# FlipDot.net
KiCad netlist of a schematic drawn in EAGLE
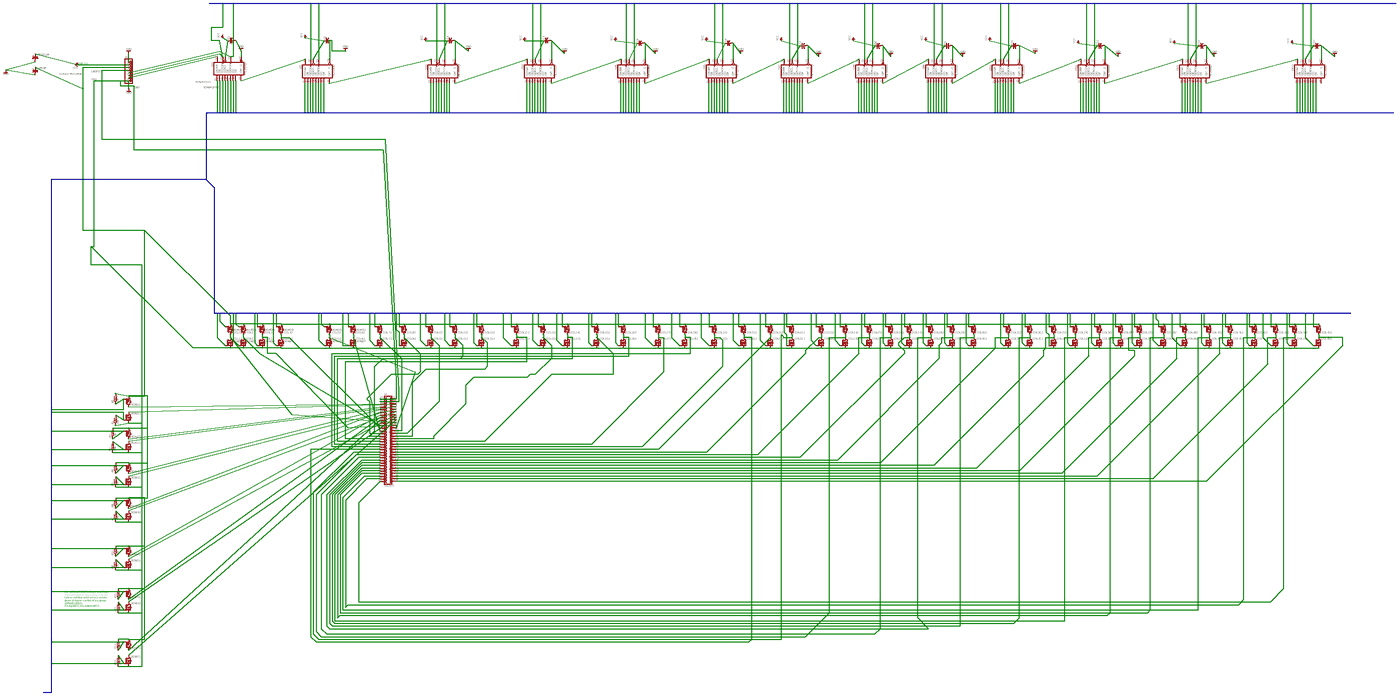
[diagram p0: schematic, sheet 1, overview]
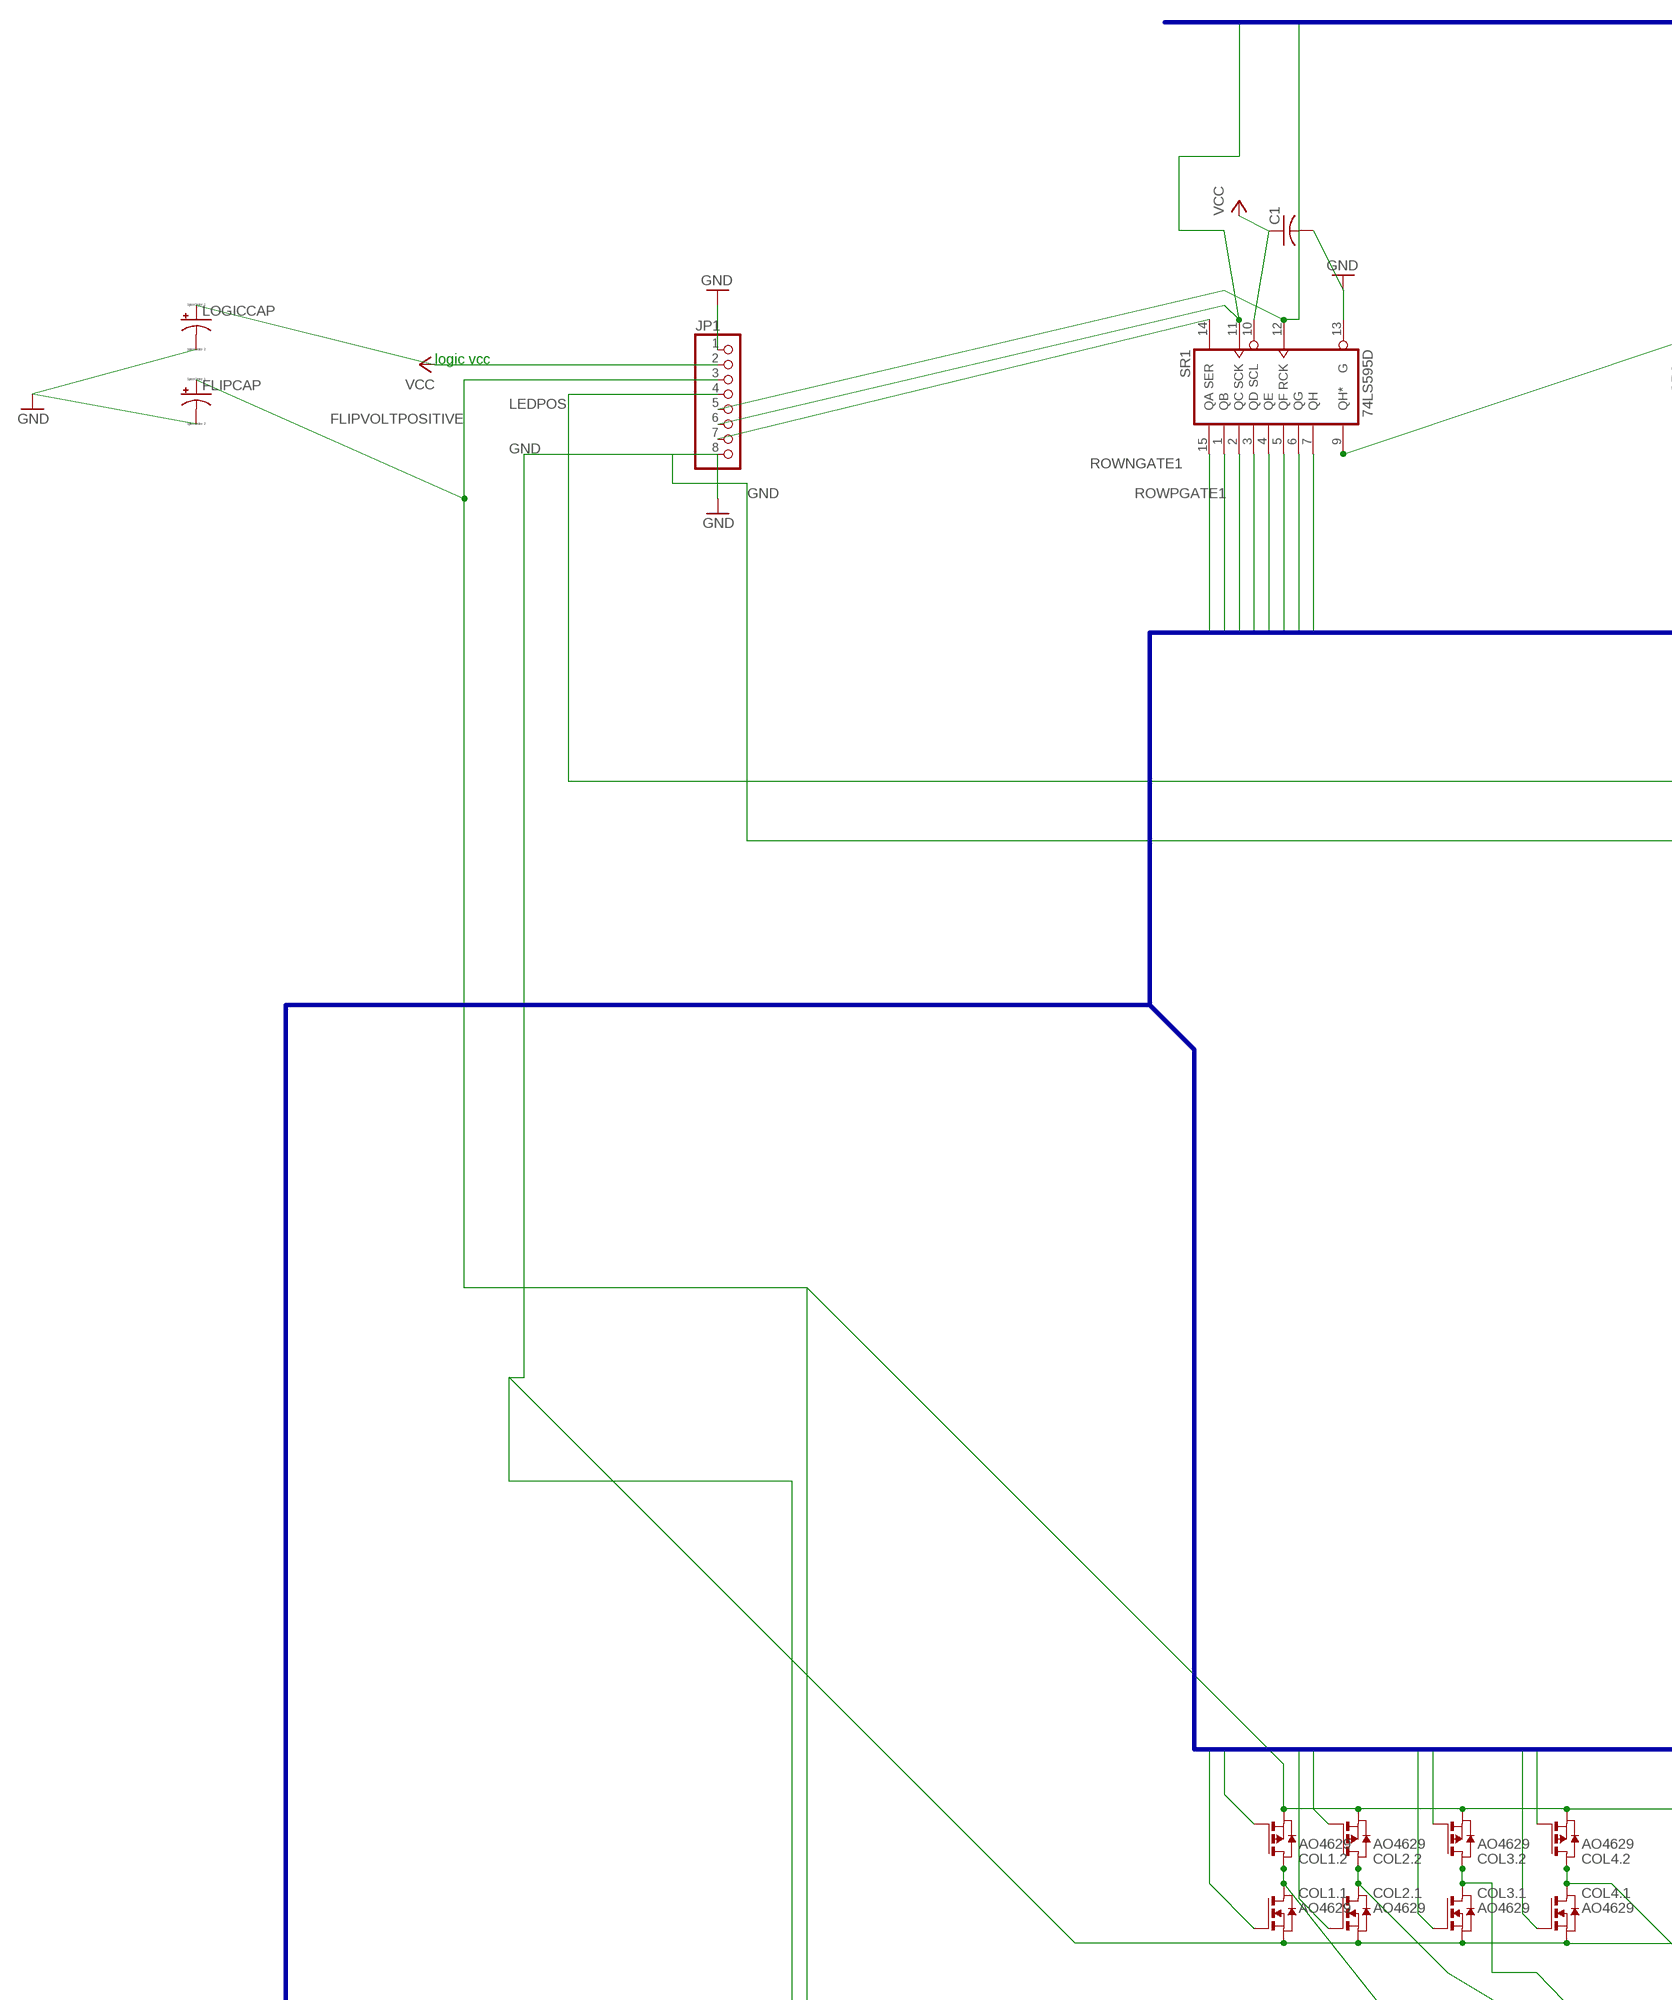
[diagram p1: schematic, sheet 1, part 1 of 8]
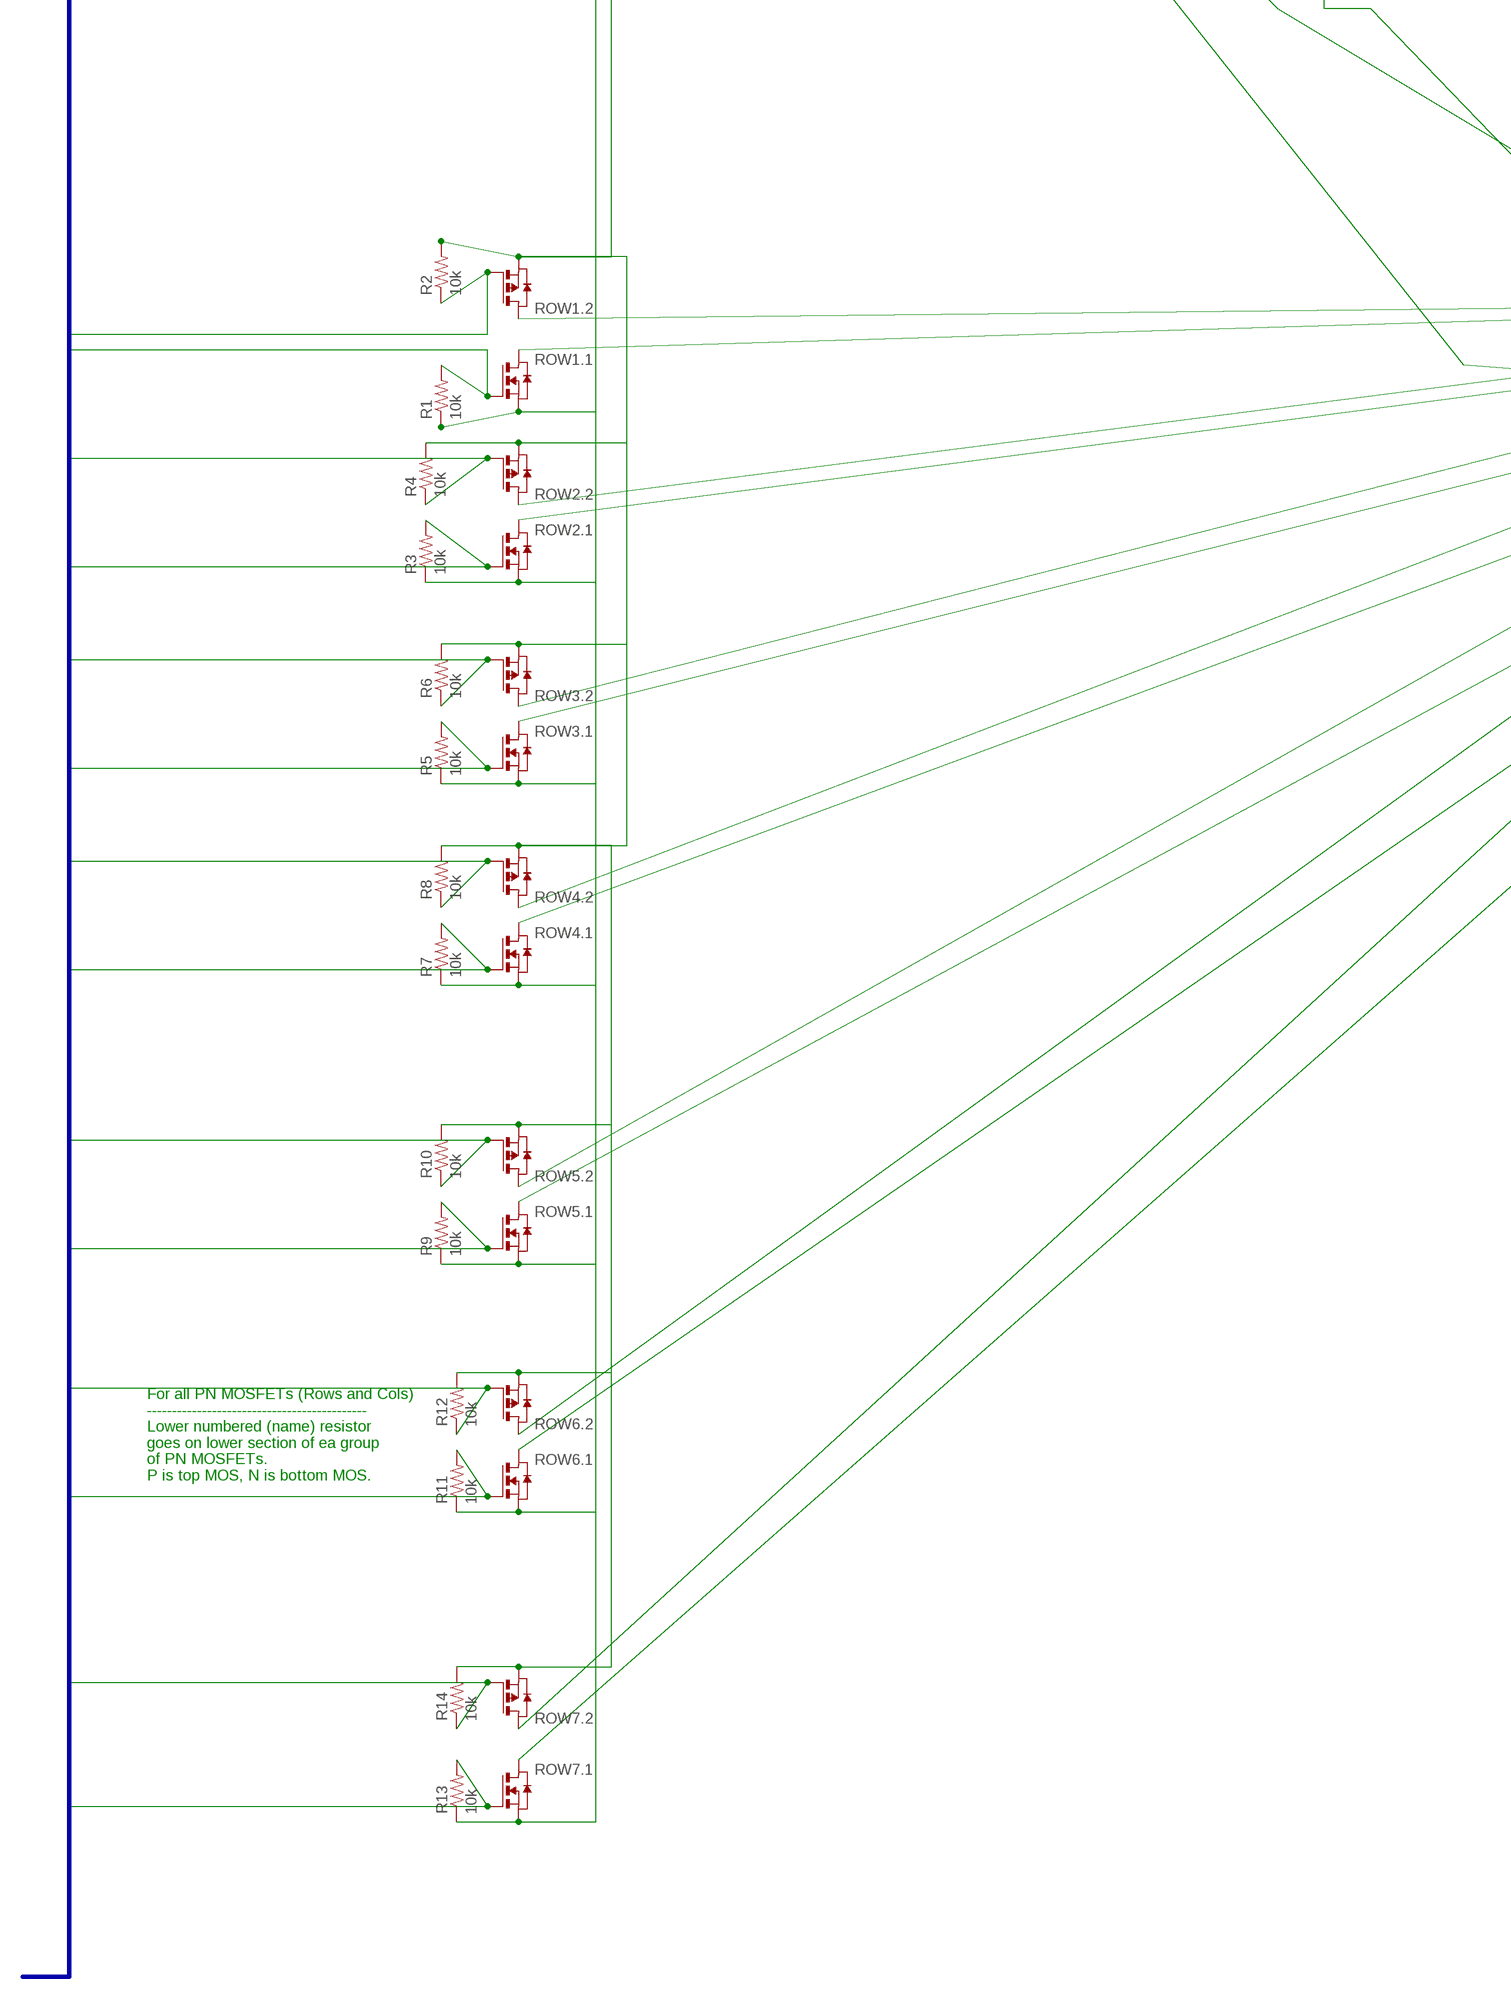
[diagram p2: schematic, sheet 1, part 2 of 8]
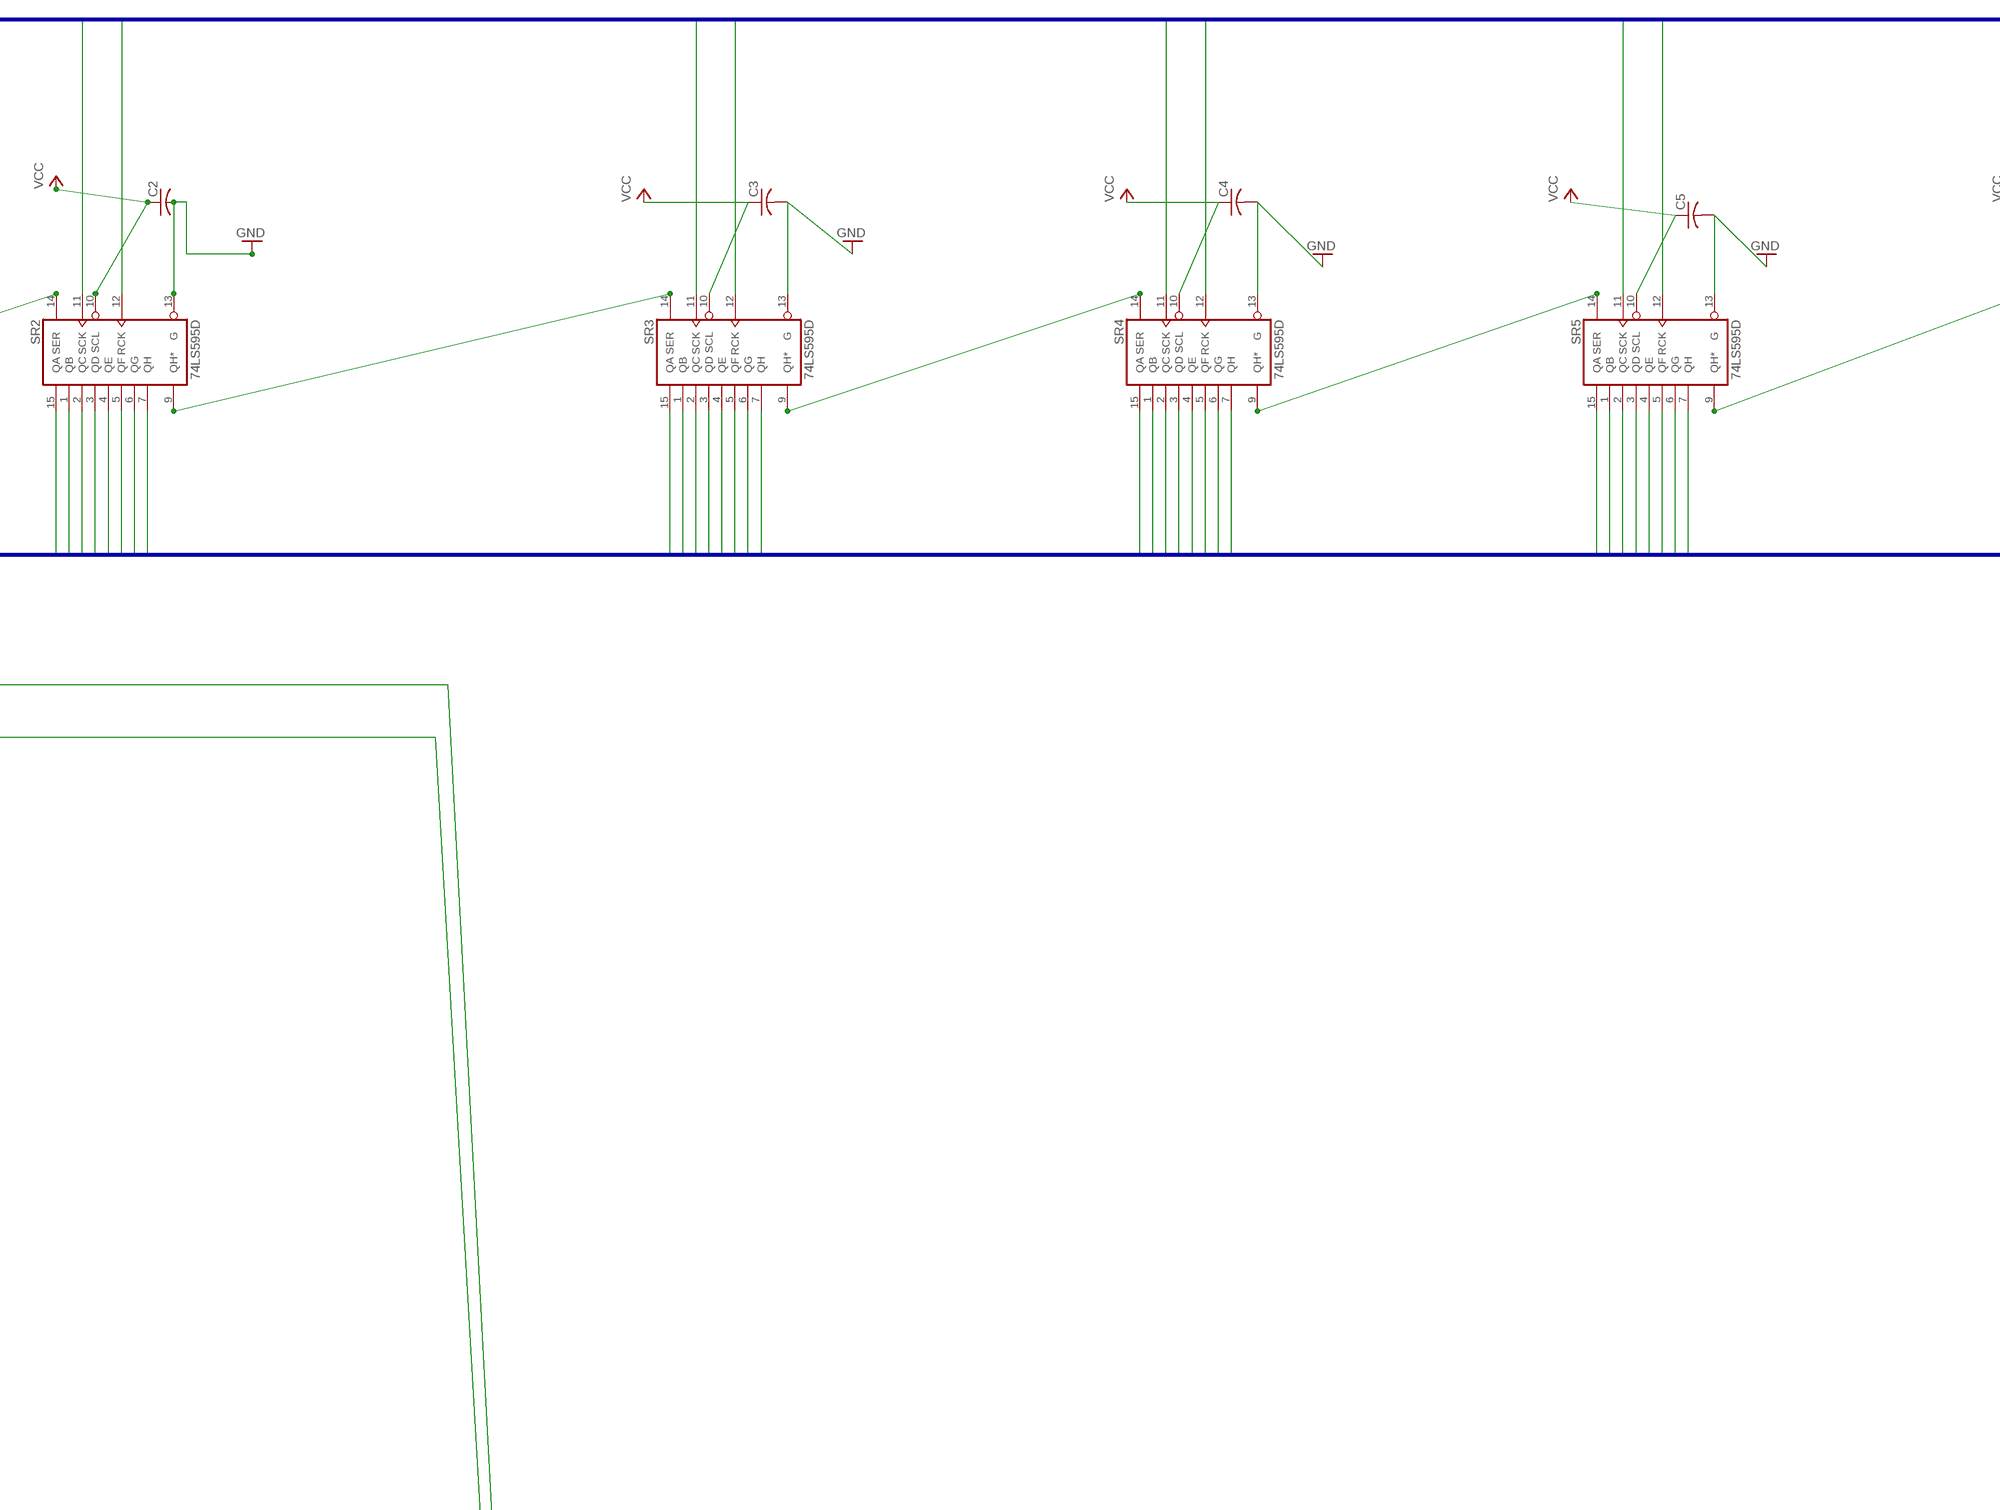
[diagram p3: schematic, sheet 1, part 3 of 8]
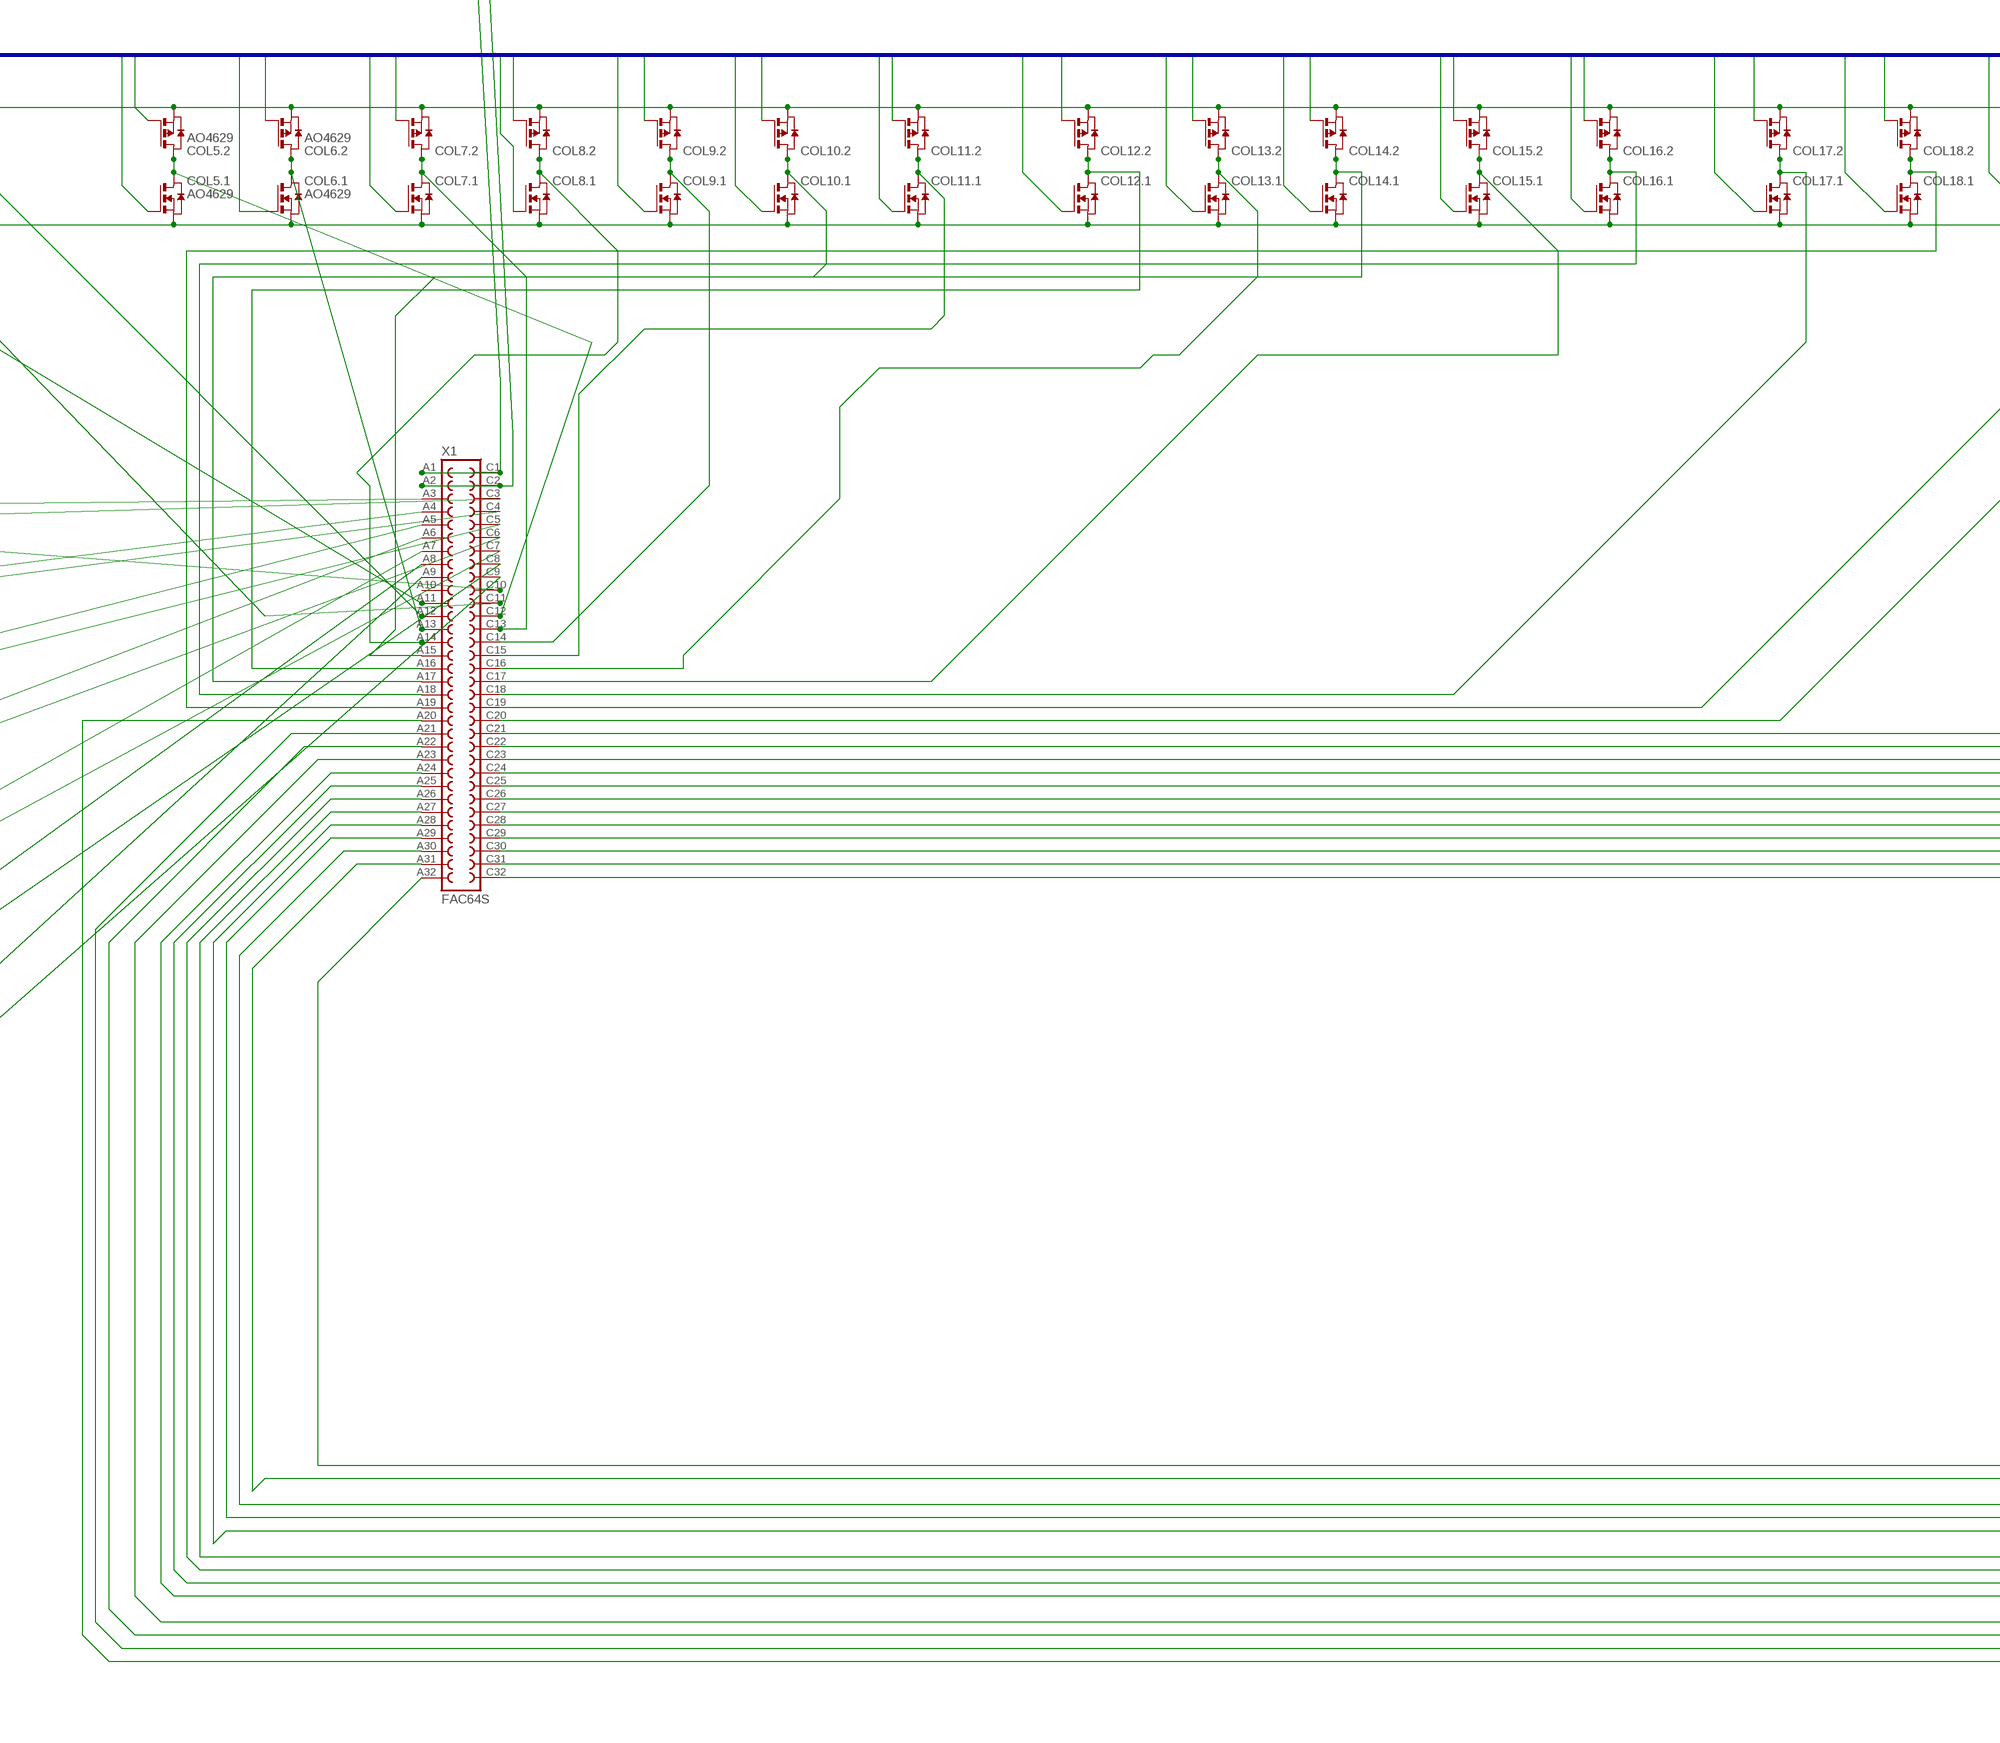
[diagram p4: schematic, sheet 1, part 4 of 8]
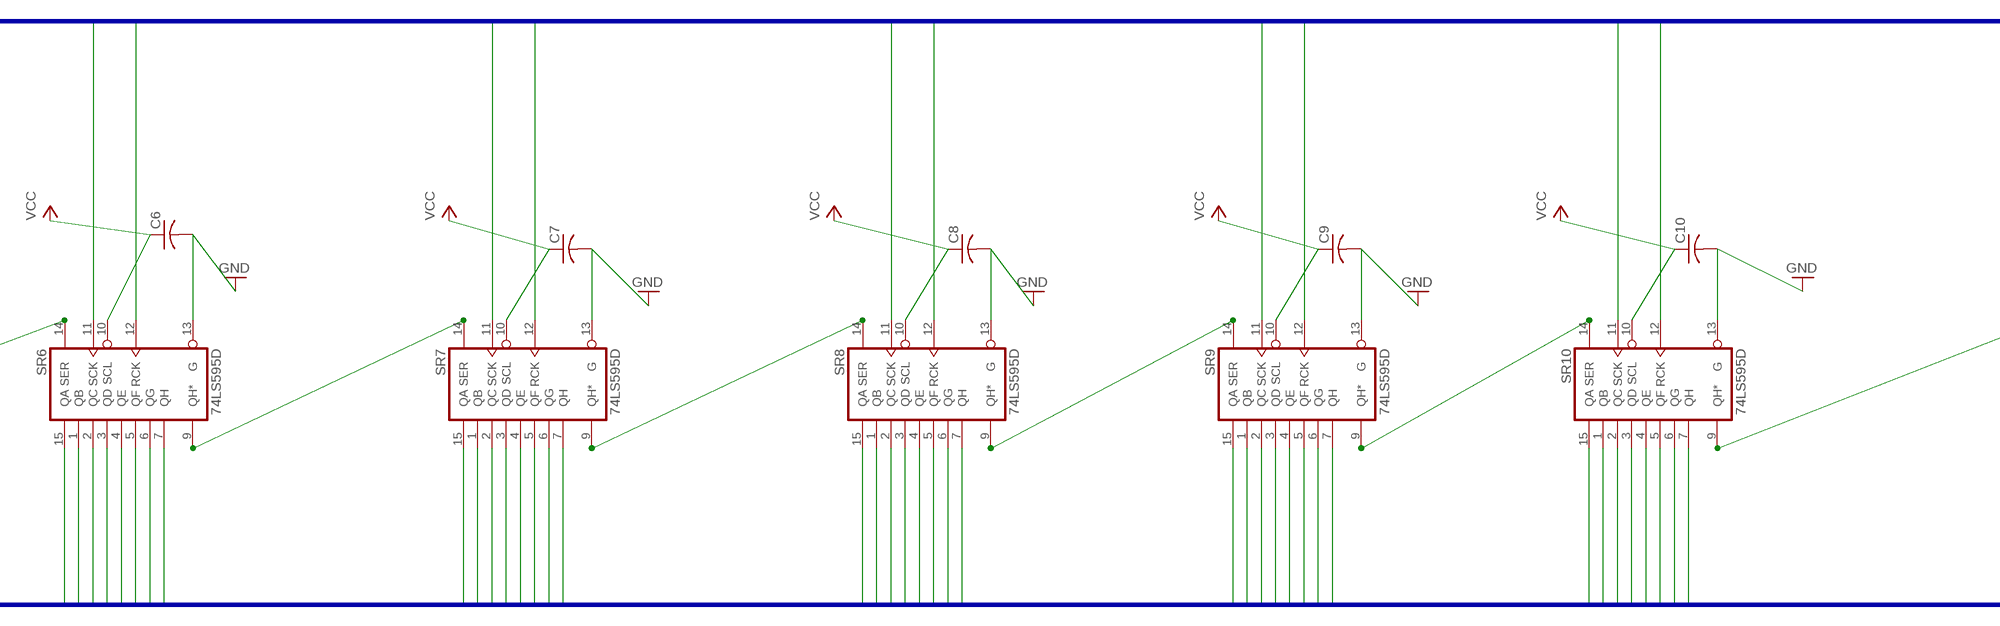
[diagram p5: schematic, sheet 1, part 5 of 8]
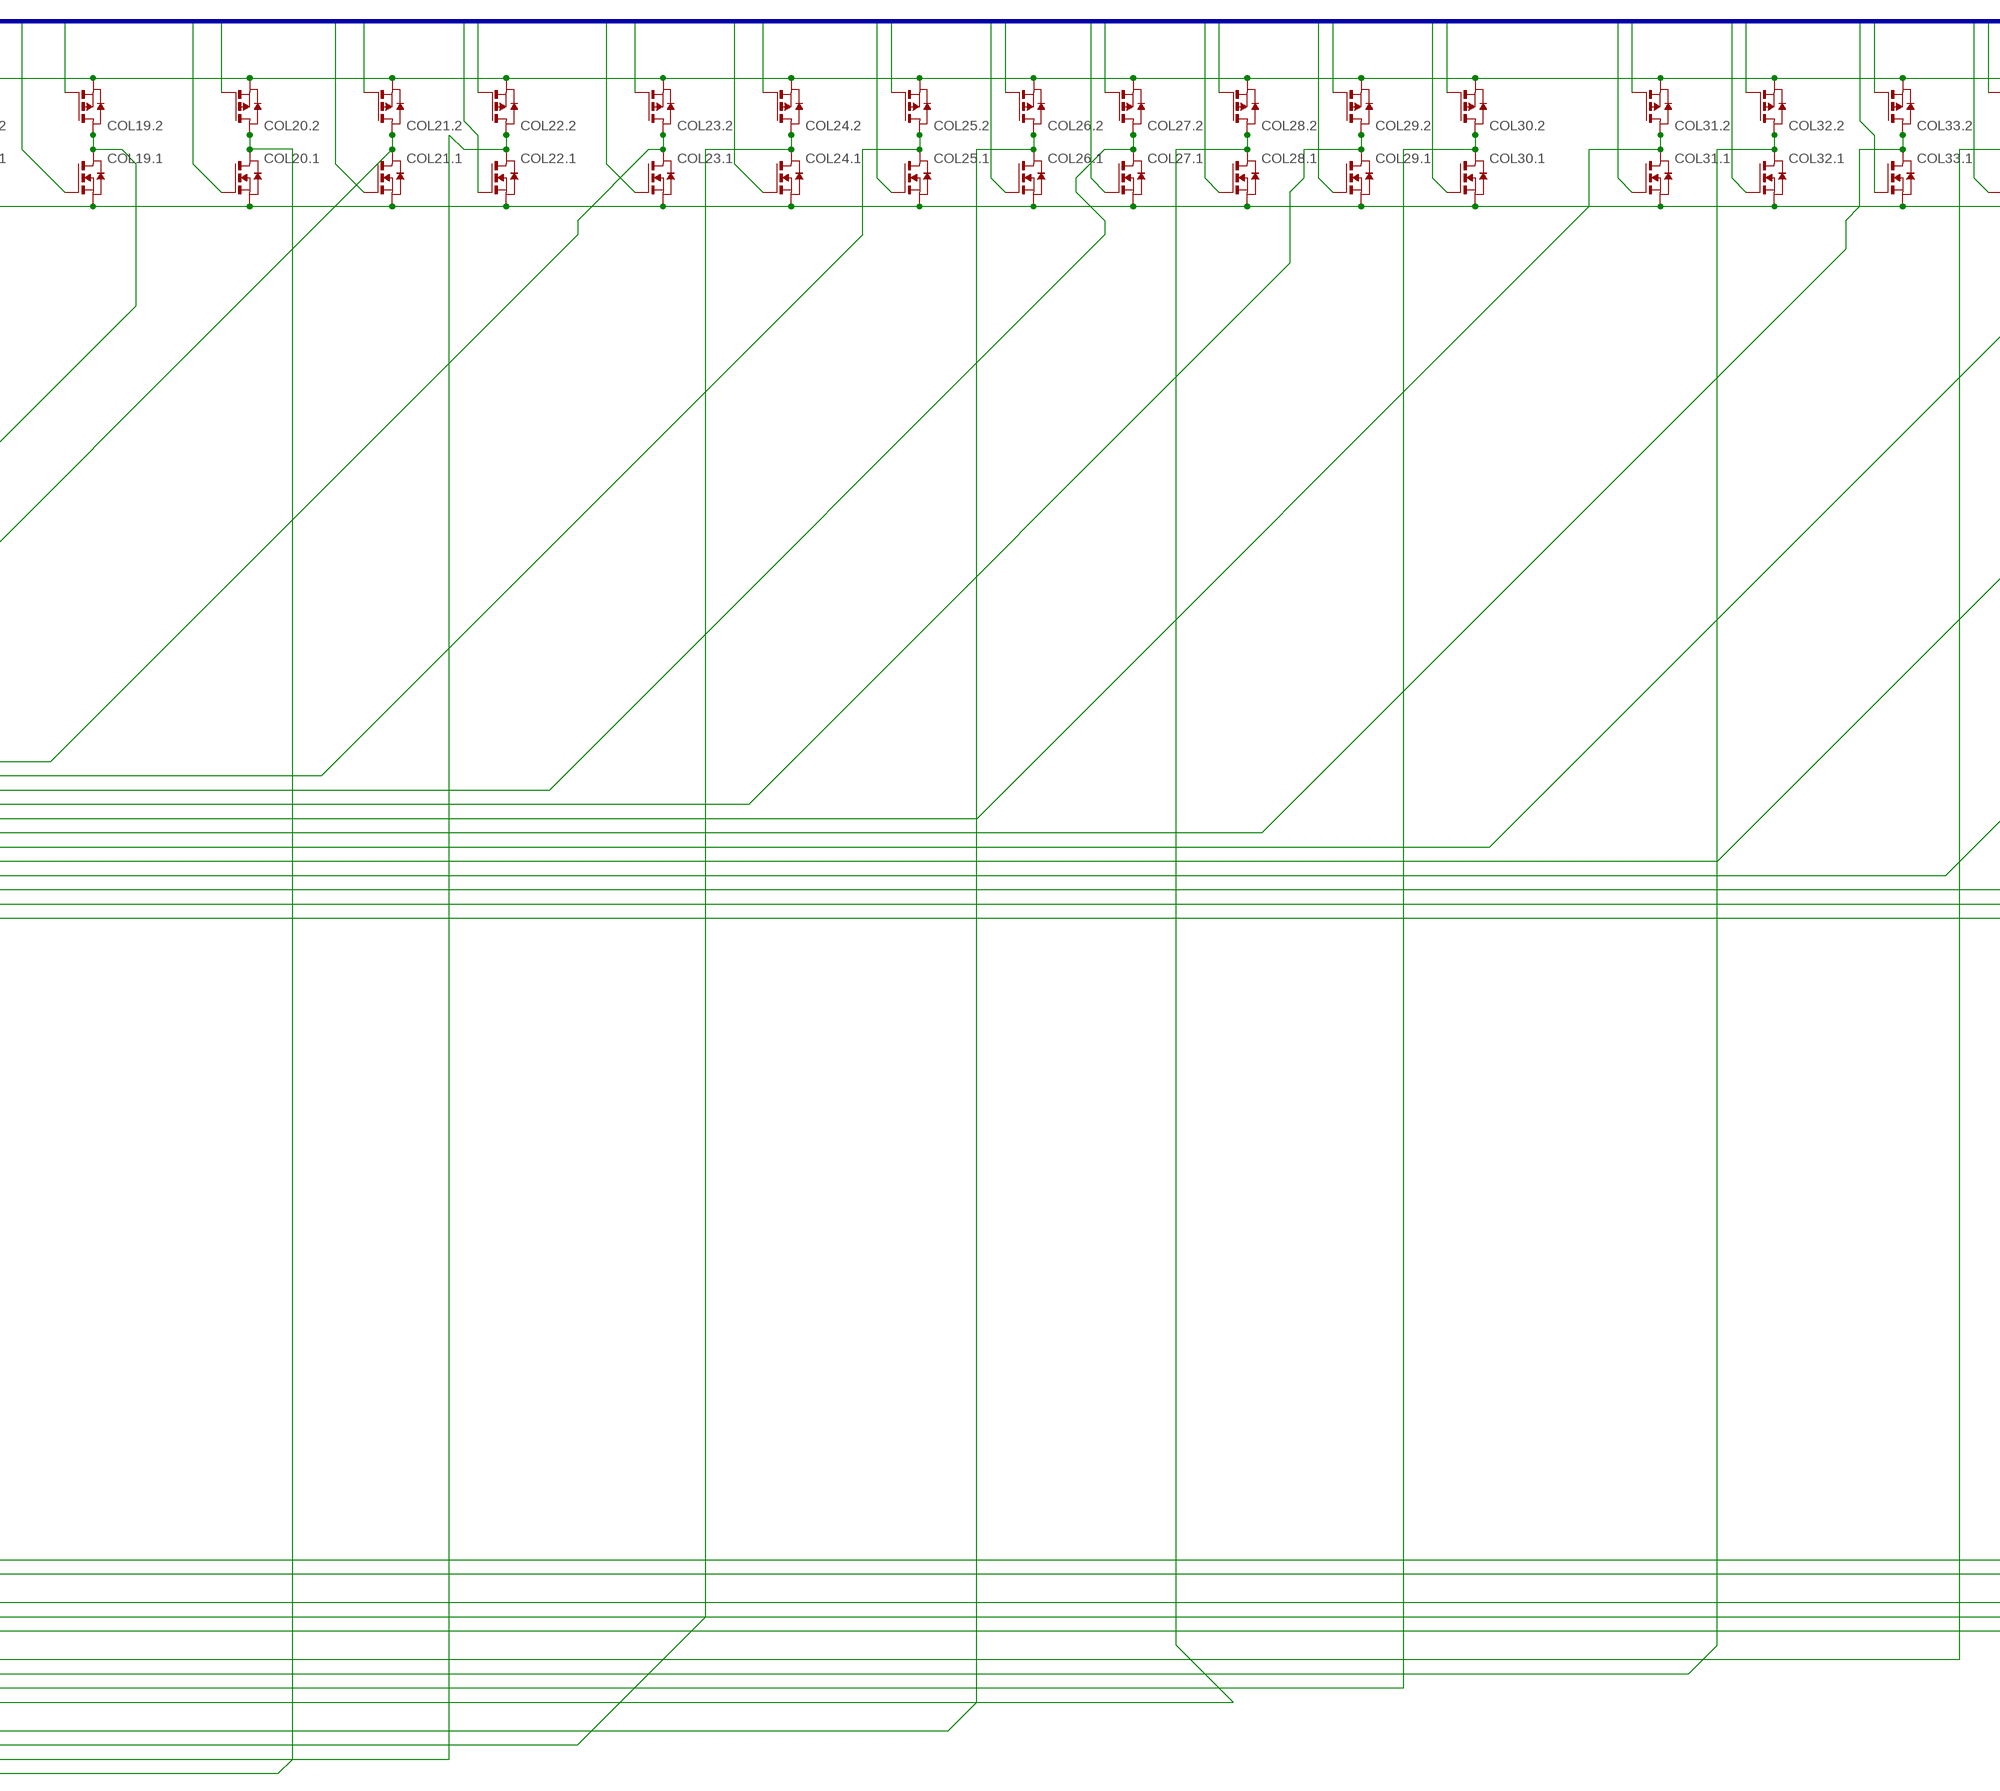
[diagram p6: schematic, sheet 1, part 6 of 8]
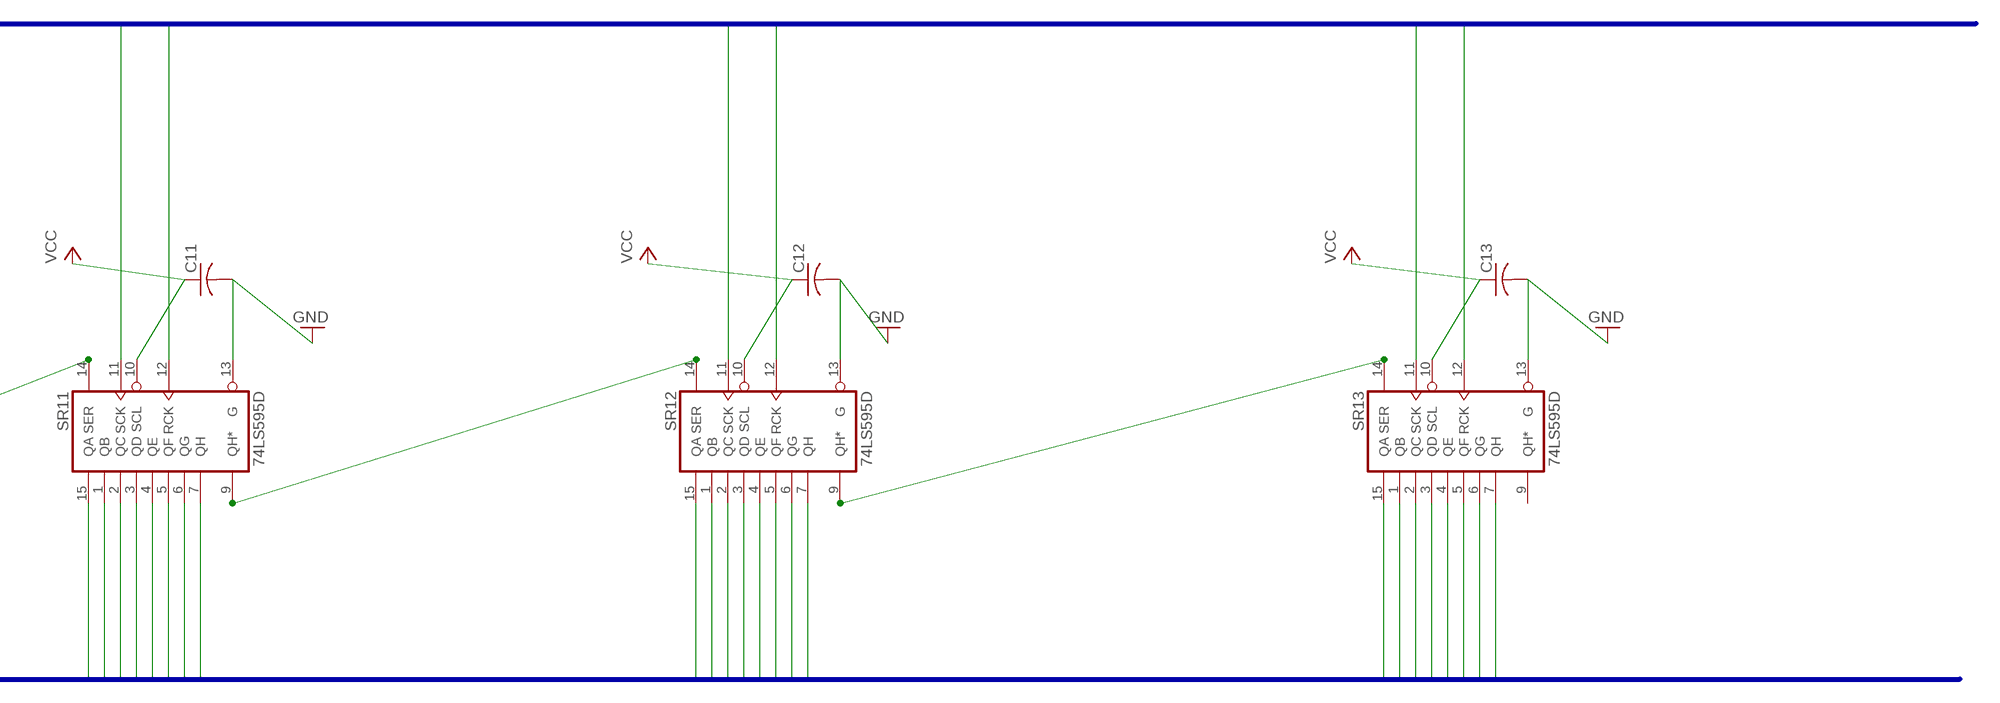
[diagram p7: schematic, sheet 1, part 7 of 8]
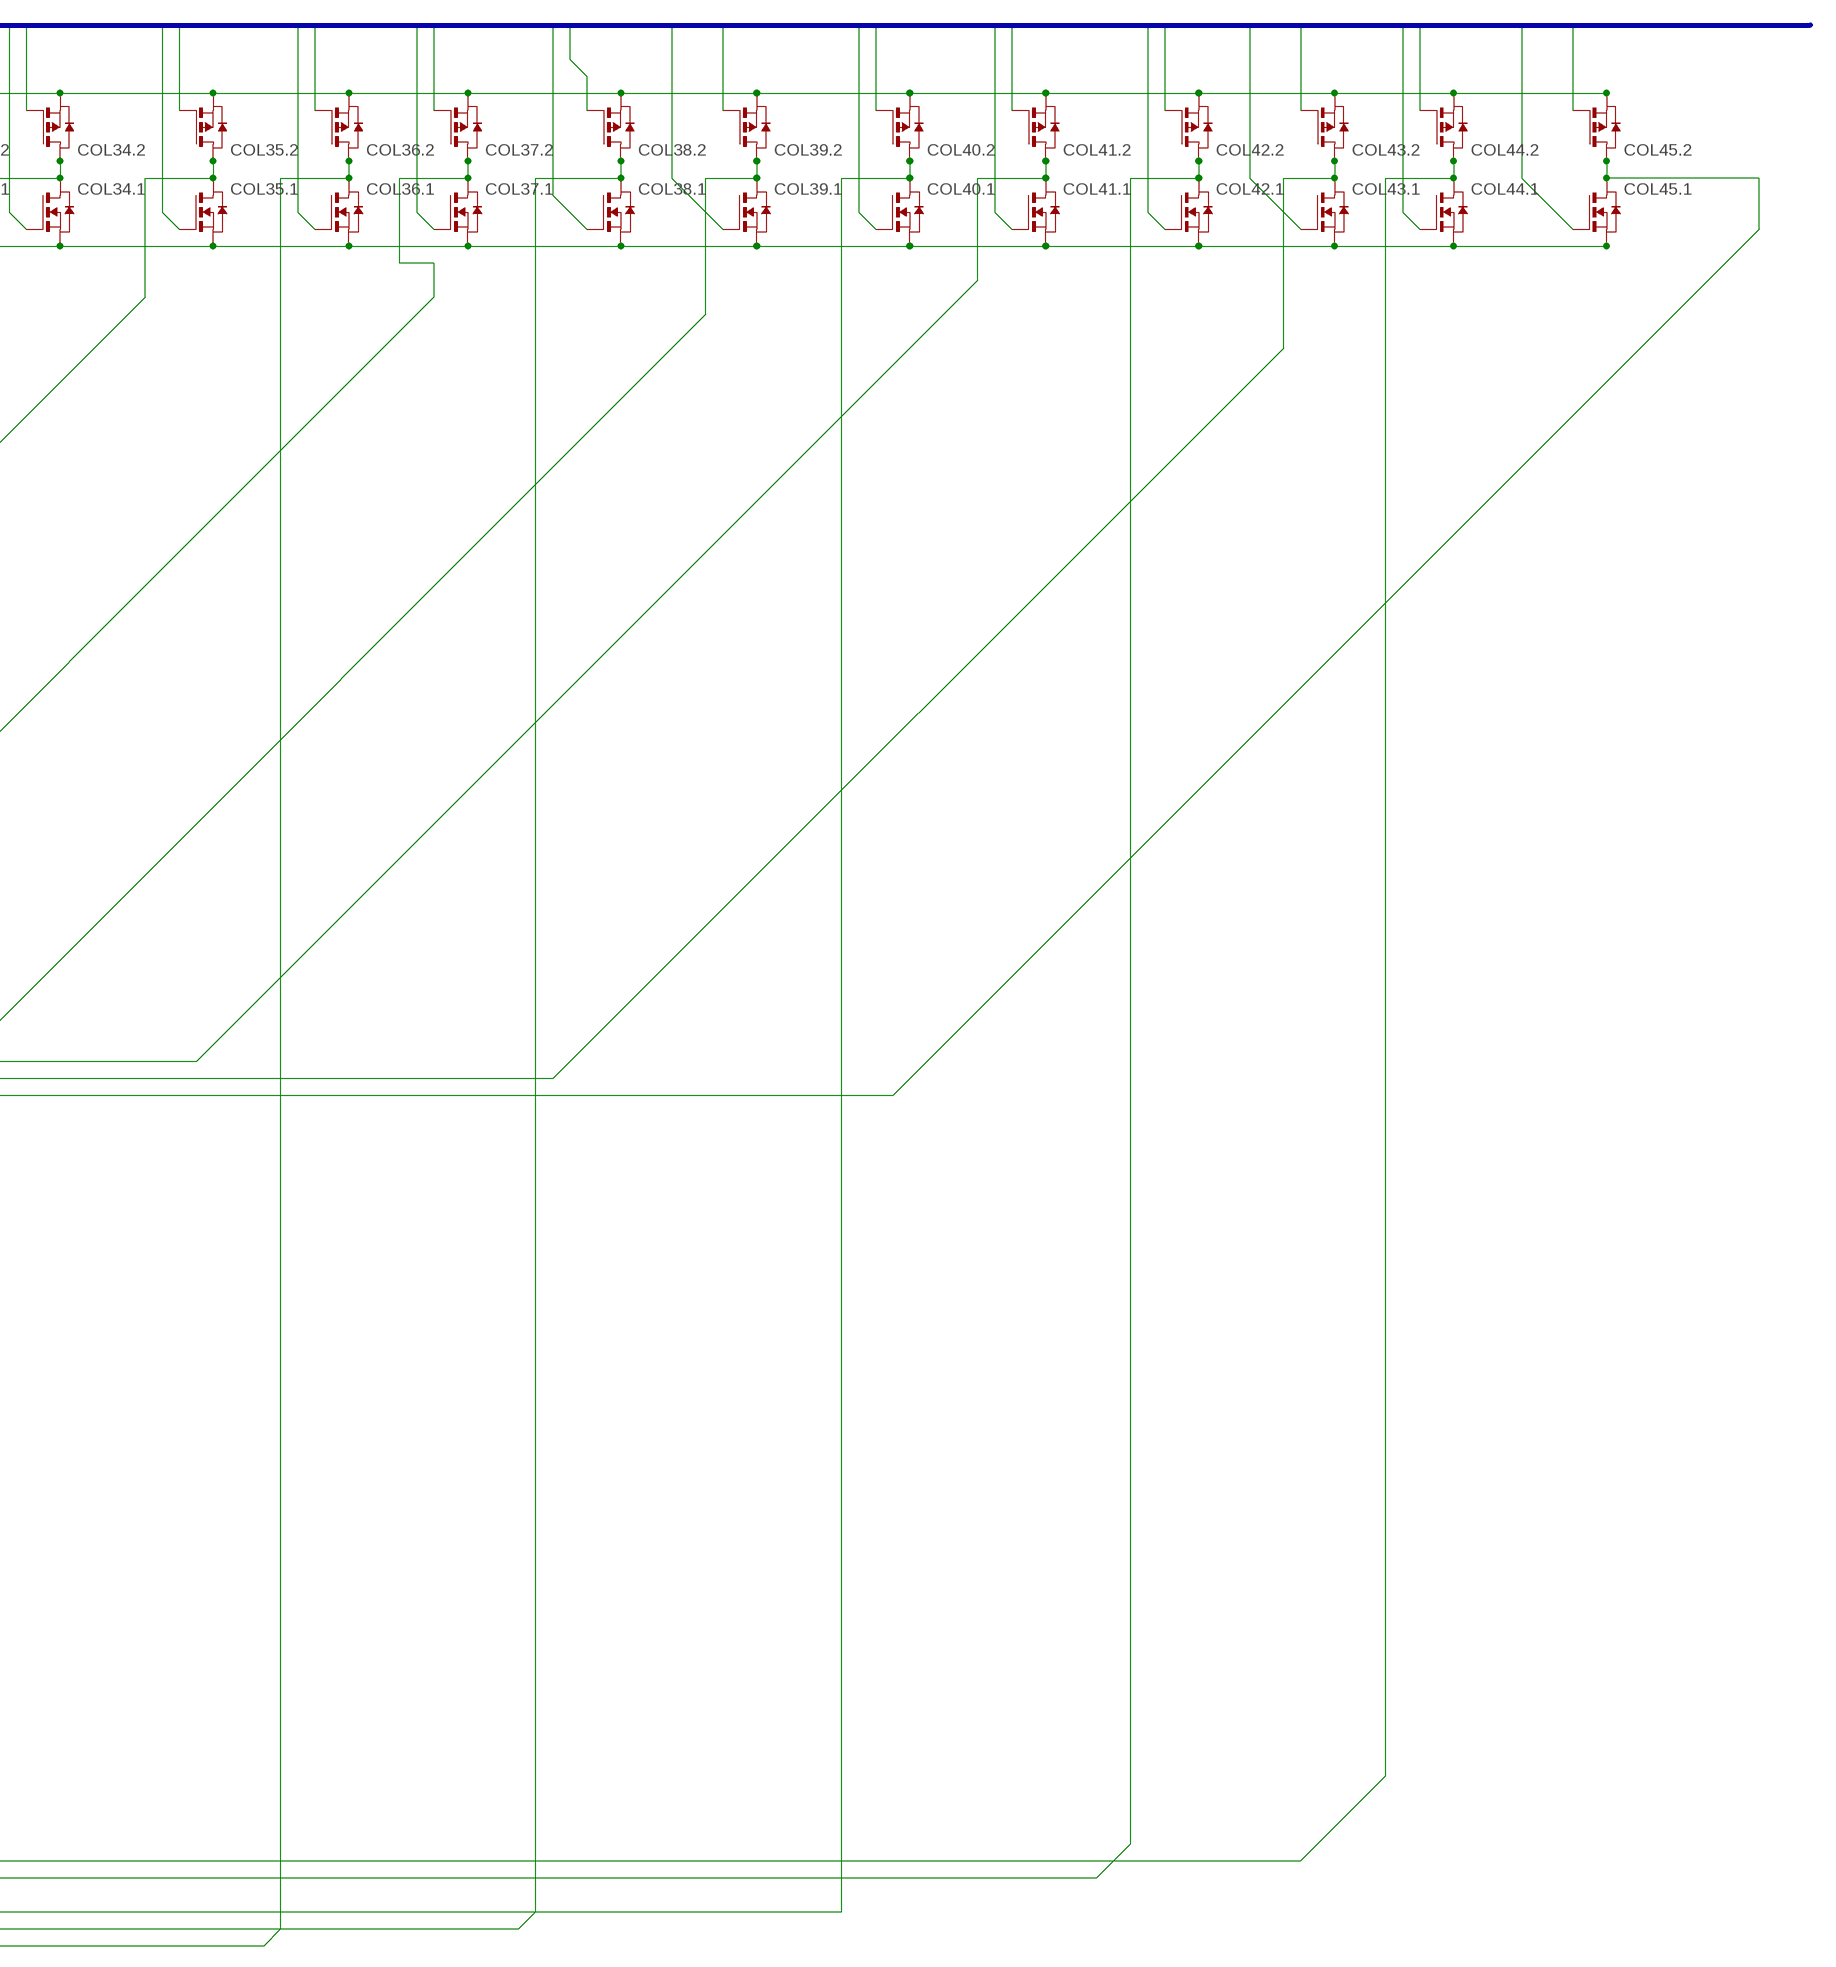
[diagram p8: schematic, sheet 1, part 8 of 8]

(export (version "E")
  (design (tool "Eeschema 10.0.6"))
  (components
    (comp (ref "C1")
      (value "C-USC2012")
      (footprint "eagle-import:C2012")
      (libsource (lib "eagle-import") (part "C-USC2012"))
    )
    (comp (ref "C2")
      (value "C-USC2012")
      (footprint "eagle-import:C2012")
      (libsource (lib "eagle-import") (part "C-USC2012"))
    )
    (comp (ref "C3")
      (value "C-USC2012")
      (footprint "eagle-import:C2012")
      (libsource (lib "eagle-import") (part "C-USC2012"))
    )
    (comp (ref "C4")
      (value "C-USC2012")
      (footprint "eagle-import:C2012")
      (libsource (lib "eagle-import") (part "C-USC2012"))
    )
    (comp (ref "C5")
      (value "C-USC2012")
      (footprint "eagle-import:C2012")
      (libsource (lib "eagle-import") (part "C-USC2012"))
    )
    (comp (ref "C6")
      (value "C-USC2012")
      (footprint "eagle-import:C2012")
      (libsource (lib "eagle-import") (part "C-USC2012"))
    )
    (comp (ref "C7")
      (value "C-USC2012")
      (footprint "eagle-import:C2012")
      (libsource (lib "eagle-import") (part "C-USC2012"))
    )
    (comp (ref "C8")
      (value "C-USC2012")
      (footprint "eagle-import:C2012")
      (libsource (lib "eagle-import") (part "C-USC2012"))
    )
    (comp (ref "C9")
      (value "C-USC2012")
      (footprint "eagle-import:C2012")
      (libsource (lib "eagle-import") (part "C-USC2012"))
    )
    (comp (ref "C10")
      (value "C-USC2012")
      (footprint "eagle-import:C2012")
      (libsource (lib "eagle-import") (part "C-USC2012"))
    )
    (comp (ref "C11")
      (value "C-USC2012")
      (footprint "eagle-import:C2012")
      (libsource (lib "eagle-import") (part "C-USC2012"))
    )
    (comp (ref "C12")
      (value "C-USC2012")
      (footprint "eagle-import:C2012")
      (libsource (lib "eagle-import") (part "C-USC2012"))
    )
    (comp (ref "C13")
      (value "C-USC2012")
      (footprint "eagle-import:C2012")
      (libsource (lib "eagle-import") (part "C-USC2012"))
    )
    (comp (ref "COL1.")
      (value "AO4629")
      (footprint "eagle-import:SO8")
      (libsource (lib "eagle-import") (part "PN_MOSFET-SO8"))
    )
    (comp (ref "COL2.")
      (value "AO4629")
      (footprint "eagle-import:SO8")
      (libsource (lib "eagle-import") (part "PN_MOSFET-SO8"))
    )
    (comp (ref "COL3.")
      (value "AO4629")
      (footprint "eagle-import:SO8")
      (libsource (lib "eagle-import") (part "PN_MOSFET-SO8"))
    )
    (comp (ref "COL4.")
      (value "AO4629")
      (footprint "eagle-import:SO8")
      (libsource (lib "eagle-import") (part "PN_MOSFET-SO8"))
    )
    (comp (ref "COL5.")
      (value "AO4629")
      (footprint "eagle-import:SO8")
      (libsource (lib "eagle-import") (part "PN_MOSFET-SO8"))
    )
    (comp (ref "COL6.")
      (value "AO4629")
      (footprint "eagle-import:SO8")
      (libsource (lib "eagle-import") (part "PN_MOSFET-SO8"))
    )
    (comp (ref "COL7.")
      (value "PN_MOSFET-SO8")
      (footprint "eagle-import:SO8")
      (libsource (lib "eagle-import") (part "PN_MOSFET-SO8"))
    )
    (comp (ref "COL8.")
      (value "PN_MOSFET-SO8")
      (footprint "eagle-import:SO8")
      (libsource (lib "eagle-import") (part "PN_MOSFET-SO8"))
    )
    (comp (ref "COL9.")
      (value "PN_MOSFET-SO8")
      (footprint "eagle-import:SO8")
      (libsource (lib "eagle-import") (part "PN_MOSFET-SO8"))
    )
    (comp (ref "COL10.")
      (value "PN_MOSFET-SO8")
      (footprint "eagle-import:SO8")
      (libsource (lib "eagle-import") (part "PN_MOSFET-SO8"))
    )
    (comp (ref "COL11.")
      (value "PN_MOSFET-SO8")
      (footprint "eagle-import:SO8")
      (libsource (lib "eagle-import") (part "PN_MOSFET-SO8"))
    )
    (comp (ref "COL12.")
      (value "PN_MOSFET-SO8")
      (footprint "eagle-import:SO8")
      (libsource (lib "eagle-import") (part "PN_MOSFET-SO8"))
    )
    (comp (ref "COL13.")
      (value "PN_MOSFET-SO8")
      (footprint "eagle-import:SO8")
      (libsource (lib "eagle-import") (part "PN_MOSFET-SO8"))
    )
    (comp (ref "COL14.")
      (value "PN_MOSFET-SO8")
      (footprint "eagle-import:SO8")
      (libsource (lib "eagle-import") (part "PN_MOSFET-SO8"))
    )
    (comp (ref "COL15.")
      (value "PN_MOSFET-SO8")
      (footprint "eagle-import:SO8")
      (libsource (lib "eagle-import") (part "PN_MOSFET-SO8"))
    )
    (comp (ref "COL16.")
      (value "PN_MOSFET-SO8")
      (footprint "eagle-import:SO8")
      (libsource (lib "eagle-import") (part "PN_MOSFET-SO8"))
    )
    (comp (ref "COL17.")
      (value "PN_MOSFET-SO8")
      (footprint "eagle-import:SO8")
      (libsource (lib "eagle-import") (part "PN_MOSFET-SO8"))
    )
    (comp (ref "COL18.")
      (value "PN_MOSFET-SO8")
      (footprint "eagle-import:SO8")
      (libsource (lib "eagle-import") (part "PN_MOSFET-SO8"))
    )
    (comp (ref "COL19.")
      (value "PN_MOSFET-SO8")
      (footprint "eagle-import:SO8")
      (libsource (lib "eagle-import") (part "PN_MOSFET-SO8"))
    )
    (comp (ref "COL20.")
      (value "PN_MOSFET-SO8")
      (footprint "eagle-import:SO8")
      (libsource (lib "eagle-import") (part "PN_MOSFET-SO8"))
    )
    (comp (ref "COL21.")
      (value "PN_MOSFET-SO8")
      (footprint "eagle-import:SO8")
      (libsource (lib "eagle-import") (part "PN_MOSFET-SO8"))
    )
    (comp (ref "COL22.")
      (value "PN_MOSFET-SO8")
      (footprint "eagle-import:SO8")
      (libsource (lib "eagle-import") (part "PN_MOSFET-SO8"))
    )
    (comp (ref "COL23.")
      (value "PN_MOSFET-SO8")
      (footprint "eagle-import:SO8")
      (libsource (lib "eagle-import") (part "PN_MOSFET-SO8"))
    )
    (comp (ref "COL24.")
      (value "PN_MOSFET-SO8")
      (footprint "eagle-import:SO8")
      (libsource (lib "eagle-import") (part "PN_MOSFET-SO8"))
    )
    (comp (ref "COL25.")
      (value "PN_MOSFET-SO8")
      (footprint "eagle-import:SO8")
      (libsource (lib "eagle-import") (part "PN_MOSFET-SO8"))
    )
    (comp (ref "COL26.")
      (value "PN_MOSFET-SO8")
      (footprint "eagle-import:SO8")
      (libsource (lib "eagle-import") (part "PN_MOSFET-SO8"))
    )
    (comp (ref "COL27.")
      (value "PN_MOSFET-SO8")
      (footprint "eagle-import:SO8")
      (libsource (lib "eagle-import") (part "PN_MOSFET-SO8"))
    )
    (comp (ref "COL28.")
      (value "PN_MOSFET-SO8")
      (footprint "eagle-import:SO8")
      (libsource (lib "eagle-import") (part "PN_MOSFET-SO8"))
    )
    (comp (ref "COL29.")
      (value "PN_MOSFET-SO8")
      (footprint "eagle-import:SO8")
      (libsource (lib "eagle-import") (part "PN_MOSFET-SO8"))
    )
    (comp (ref "COL30.")
      (value "PN_MOSFET-SO8")
      (footprint "eagle-import:SO8")
      (libsource (lib "eagle-import") (part "PN_MOSFET-SO8"))
    )
    (comp (ref "COL31.")
      (value "PN_MOSFET-SO8")
      (footprint "eagle-import:SO8")
      (libsource (lib "eagle-import") (part "PN_MOSFET-SO8"))
    )
    (comp (ref "COL32.")
      (value "PN_MOSFET-SO8")
      (footprint "eagle-import:SO8")
      (libsource (lib "eagle-import") (part "PN_MOSFET-SO8"))
    )
    (comp (ref "COL33.")
      (value "PN_MOSFET-SO8")
      (footprint "eagle-import:SO8")
      (libsource (lib "eagle-import") (part "PN_MOSFET-SO8"))
    )
    (comp (ref "COL34.")
      (value "PN_MOSFET-SO8")
      (footprint "eagle-import:SO8")
      (libsource (lib "eagle-import") (part "PN_MOSFET-SO8"))
    )
    (comp (ref "COL35.")
      (value "PN_MOSFET-SO8")
      (footprint "eagle-import:SO8")
      (libsource (lib "eagle-import") (part "PN_MOSFET-SO8"))
    )
    (comp (ref "COL36.")
      (value "PN_MOSFET-SO8")
      (footprint "eagle-import:SO8")
      (libsource (lib "eagle-import") (part "PN_MOSFET-SO8"))
    )
    (comp (ref "COL37.")
      (value "PN_MOSFET-SO8")
      (footprint "eagle-import:SO8")
      (libsource (lib "eagle-import") (part "PN_MOSFET-SO8"))
    )
    (comp (ref "COL38.")
      (value "PN_MOSFET-SO8")
      (footprint "eagle-import:SO8")
      (libsource (lib "eagle-import") (part "PN_MOSFET-SO8"))
    )
    (comp (ref "COL39.")
      (value "PN_MOSFET-SO8")
      (footprint "eagle-import:SO8")
      (libsource (lib "eagle-import") (part "PN_MOSFET-SO8"))
    )
    (comp (ref "COL40.")
      (value "PN_MOSFET-SO8")
      (footprint "eagle-import:SO8")
      (libsource (lib "eagle-import") (part "PN_MOSFET-SO8"))
    )
    (comp (ref "COL41.")
      (value "PN_MOSFET-SO8")
      (footprint "eagle-import:SO8")
      (libsource (lib "eagle-import") (part "PN_MOSFET-SO8"))
    )
    (comp (ref "COL42.")
      (value "PN_MOSFET-SO8")
      (footprint "eagle-import:SO8")
      (libsource (lib "eagle-import") (part "PN_MOSFET-SO8"))
    )
    (comp (ref "COL43.")
      (value "PN_MOSFET-SO8")
      (footprint "eagle-import:SO8")
      (libsource (lib "eagle-import") (part "PN_MOSFET-SO8"))
    )
    (comp (ref "COL44.")
      (value "PN_MOSFET-SO8")
      (footprint "eagle-import:SO8")
      (libsource (lib "eagle-import") (part "PN_MOSFET-SO8"))
    )
    (comp (ref "COL45.")
      (value "PN_MOSFET-SO8")
      (footprint "eagle-import:SO8")
      (libsource (lib "eagle-import") (part "PN_MOSFET-SO8"))
    )
    (comp (ref "FLIPCAP")
      (value "CPOL-USE5-10.5")
      (footprint "eagle-import:E5-10,5")
      (libsource (lib "eagle-import") (part "CPOL-USE5-10.5"))
    )
    (comp (ref "JP1")
      (value "PINHD-1X8")
      (footprint "eagle-import:1X08")
      (libsource (lib "eagle-import") (part "PINHD-1X8"))
    )
    (comp (ref "LOGICCAP")
      (value "CPOL-USE5-10.5")
      (footprint "eagle-import:E5-10,5")
      (libsource (lib "eagle-import") (part "CPOL-USE5-10.5"))
    )
    (comp (ref "R1")
      (value "10k")
      (footprint "eagle-import:R2012")
      (libsource (lib "eagle-import") (part "R-US_R2012"))
    )
    (comp (ref "R2")
      (value "10k")
      (footprint "eagle-import:R2012")
      (libsource (lib "eagle-import") (part "R-US_R2012"))
    )
    (comp (ref "R3")
      (value "10k")
      (footprint "eagle-import:R2012")
      (libsource (lib "eagle-import") (part "R-US_R2012"))
    )
    (comp (ref "R4")
      (value "10k")
      (footprint "eagle-import:R2012")
      (libsource (lib "eagle-import") (part "R-US_R2012"))
    )
    (comp (ref "R5")
      (value "10k")
      (footprint "eagle-import:R2012")
      (libsource (lib "eagle-import") (part "R-US_R2012"))
    )
    (comp (ref "R6")
      (value "10k")
      (footprint "eagle-import:R2012")
      (libsource (lib "eagle-import") (part "R-US_R2012"))
    )
    (comp (ref "R7")
      (value "10k")
      (footprint "eagle-import:R2012")
      (libsource (lib "eagle-import") (part "R-US_R2012"))
    )
    (comp (ref "R8")
      (value "10k")
      (footprint "eagle-import:R2012")
      (libsource (lib "eagle-import") (part "R-US_R2012"))
    )
    (comp (ref "R9")
      (value "10k")
      (footprint "eagle-import:R2012")
      (libsource (lib "eagle-import") (part "R-US_R2012"))
    )
    (comp (ref "R10")
      (value "10k")
      (footprint "eagle-import:R2012")
      (libsource (lib "eagle-import") (part "R-US_R2012"))
    )
    (comp (ref "R11")
      (value "10k")
      (footprint "eagle-import:R2012")
      (libsource (lib "eagle-import") (part "R-US_R2012"))
    )
    (comp (ref "R12")
      (value "10k")
      (footprint "eagle-import:R2012")
      (libsource (lib "eagle-import") (part "R-US_R2012"))
    )
    (comp (ref "R13")
      (value "10k")
      (footprint "eagle-import:R2012")
      (libsource (lib "eagle-import") (part "R-US_R2012"))
    )
    (comp (ref "R14")
      (value "10k")
      (footprint "eagle-import:R2012")
      (libsource (lib "eagle-import") (part "R-US_R2012"))
    )
    (comp (ref "ROW1.")
      (value "PN_MOSFET-SO8")
      (footprint "eagle-import:SO8")
      (libsource (lib "eagle-import") (part "PN_MOSFET-SO8"))
    )
    (comp (ref "ROW2.")
      (value "PN_MOSFET-SO8")
      (footprint "eagle-import:SO8")
      (libsource (lib "eagle-import") (part "PN_MOSFET-SO8"))
    )
    (comp (ref "ROW3.")
      (value "PN_MOSFET-SO8")
      (footprint "eagle-import:SO8")
      (libsource (lib "eagle-import") (part "PN_MOSFET-SO8"))
    )
    (comp (ref "ROW4.")
      (value "PN_MOSFET-SO8")
      (footprint "eagle-import:SO8")
      (libsource (lib "eagle-import") (part "PN_MOSFET-SO8"))
    )
    (comp (ref "ROW5.")
      (value "PN_MOSFET-SO8")
      (footprint "eagle-import:SO8")
      (libsource (lib "eagle-import") (part "PN_MOSFET-SO8"))
    )
    (comp (ref "ROW6.")
      (value "PN_MOSFET-SO8")
      (footprint "eagle-import:SO8")
      (libsource (lib "eagle-import") (part "PN_MOSFET-SO8"))
    )
    (comp (ref "ROW7.")
      (value "PN_MOSFET-SO8")
      (footprint "eagle-import:SO8")
      (libsource (lib "eagle-import") (part "PN_MOSFET-SO8"))
    )
    (comp (ref "SR1")
      (value "74LS595D")
      (footprint "eagle-import:SO16")
      (libsource (lib "eagle-import") (part "74595DLS"))
    )
    (comp (ref "SR2")
      (value "74LS595D")
      (footprint "eagle-import:SO16")
      (libsource (lib "eagle-import") (part "74595DLS"))
    )
    (comp (ref "SR3")
      (value "74LS595D")
      (footprint "eagle-import:SO16")
      (libsource (lib "eagle-import") (part "74595DLS"))
    )
    (comp (ref "SR4")
      (value "74LS595D")
      (footprint "eagle-import:SO16")
      (libsource (lib "eagle-import") (part "74595DLS"))
    )
    (comp (ref "SR5")
      (value "74LS595D")
      (footprint "eagle-import:SO16")
      (libsource (lib "eagle-import") (part "74595DLS"))
    )
    (comp (ref "SR6")
      (value "74LS595D")
      (footprint "eagle-import:SO16")
      (libsource (lib "eagle-import") (part "74595DLS"))
    )
    (comp (ref "SR7")
      (value "74LS595D")
      (footprint "eagle-import:SO16")
      (libsource (lib "eagle-import") (part "74595DLS"))
    )
    (comp (ref "SR8")
      (value "74LS595D")
      (footprint "eagle-import:SO16")
      (libsource (lib "eagle-import") (part "74595DLS"))
    )
    (comp (ref "SR9")
      (value "74LS595D")
      (footprint "eagle-import:SO16")
      (libsource (lib "eagle-import") (part "74595DLS"))
    )
    (comp (ref "SR10")
      (value "74LS595D")
      (footprint "eagle-import:SO16")
      (libsource (lib "eagle-import") (part "74595DLS"))
    )
    (comp (ref "SR11")
      (value "74LS595D")
      (footprint "eagle-import:SO16")
      (libsource (lib "eagle-import") (part "74595DLS"))
    )
    (comp (ref "SR12")
      (value "74LS595D")
      (footprint "eagle-import:SO16")
      (libsource (lib "eagle-import") (part "74595DLS"))
    )
    (comp (ref "SR13")
      (value "74LS595D")
      (footprint "eagle-import:SO16")
      (libsource (lib "eagle-import") (part "74595DLS"))
    )
    (comp (ref "X1")
      (value "FAC64S")
      (footprint "eagle-import:FAC64S")
      (libsource (lib "eagle-import") (part "FAC64S"))
    )
  )
  (nets
    (net (code "1") (name "/COLNGATE1") (class "Default")
      (node (ref "COL1.") (pin "2") (pinfunction "G_2") (pintype "passive"))
      (node (ref "SR2") (pin "6") (pinfunction "QG_6") (pintype "tri_state"))
    )
    (net (code "2") (name "/COLNGATE2") (class "Default")
      (node (ref "COL2.") (pin "2") (pinfunction "G_2") (pintype "passive"))
      (node (ref "SR3") (pin "15") (pinfunction "QA_15") (pintype "tri_state"))
    )
    (net (code "3") (name "/COLNGATE3") (class "Default")
      (node (ref "COL3.") (pin "2") (pinfunction "G_2") (pintype "passive"))
      (node (ref "SR3") (pin "2") (pinfunction "QC_2") (pintype "tri_state"))
    )
    (net (code "4") (name "/COLNGATE4") (class "Default")
      (node (ref "COL4.") (pin "2") (pinfunction "G_2") (pintype "passive"))
      (node (ref "SR3") (pin "4") (pinfunction "QE_4") (pintype "tri_state"))
    )
    (net (code "5") (name "/COLNGATE5") (class "Default")
      (node (ref "COL5.") (pin "2") (pinfunction "G_2") (pintype "passive"))
      (node (ref "SR3") (pin "6") (pinfunction "QG_6") (pintype "tri_state"))
    )
    (net (code "6") (name "/COLNGATE6") (class "Default")
      (node (ref "COL6.") (pin "2") (pinfunction "G_2") (pintype "passive"))
      (node (ref "SR4") (pin "15") (pinfunction "QA_15") (pintype "tri_state"))
    )
    (net (code "7") (name "/COLNGATE7") (class "Default")
      (node (ref "COL7.") (pin "2") (pinfunction "G_2") (pintype "passive"))
      (node (ref "SR4") (pin "2") (pinfunction "QC_2") (pintype "tri_state"))
    )
    (net (code "8") (name "/COLNGATE8") (class "Default")
      (node (ref "COL8.") (pin "2") (pinfunction "G_2") (pintype "passive"))
      (node (ref "SR4") (pin "4") (pinfunction "QE_4") (pintype "tri_state"))
    )
    (net (code "9") (name "/COLNGATE9") (class "Default")
      (node (ref "COL9.") (pin "2") (pinfunction "G_2") (pintype "passive"))
      (node (ref "SR4") (pin "6") (pinfunction "QG_6") (pintype "tri_state"))
    )
    (net (code "10") (name "/COLNGATE10") (class "Default")
      (node (ref "COL10.") (pin "2") (pinfunction "G_2") (pintype "passive"))
      (node (ref "SR5") (pin "15") (pinfunction "QA_15") (pintype "tri_state"))
    )
    (net (code "11") (name "/COLNGATE11") (class "Default")
      (node (ref "COL11.") (pin "2") (pinfunction "G_2") (pintype "passive"))
      (node (ref "SR5") (pin "2") (pinfunction "QC_2") (pintype "tri_state"))
    )
    (net (code "12") (name "/COLNGATE12") (class "Default")
      (node (ref "COL12.") (pin "2") (pinfunction "G_2") (pintype "passive"))
      (node (ref "SR5") (pin "4") (pinfunction "QE_4") (pintype "tri_state"))
    )
    (net (code "13") (name "/COLNGATE13") (class "Default")
      (node (ref "COL13.") (pin "2") (pinfunction "G_2") (pintype "passive"))
      (node (ref "SR5") (pin "6") (pinfunction "QG_6") (pintype "tri_state"))
    )
    (net (code "14") (name "/COLNGATE14") (class "Default")
      (node (ref "COL14.") (pin "2") (pinfunction "G_2") (pintype "passive"))
      (node (ref "SR6") (pin "15") (pinfunction "QA_15") (pintype "tri_state"))
    )
    (net (code "15") (name "/COLNGATE15") (class "Default")
      (node (ref "COL15.") (pin "2") (pinfunction "G_2") (pintype "passive"))
      (node (ref "SR6") (pin "2") (pinfunction "QC_2") (pintype "tri_state"))
    )
    (net (code "16") (name "/COLNGATE16") (class "Default")
      (node (ref "COL16.") (pin "2") (pinfunction "G_2") (pintype "passive"))
      (node (ref "SR6") (pin "4") (pinfunction "QE_4") (pintype "tri_state"))
    )
    (net (code "17") (name "/COLNGATE17") (class "Default")
      (node (ref "COL17.") (pin "2") (pinfunction "G_2") (pintype "passive"))
      (node (ref "SR6") (pin "6") (pinfunction "QG_6") (pintype "tri_state"))
    )
    (net (code "18") (name "/COLNGATE18") (class "Default")
      (node (ref "COL18.") (pin "2") (pinfunction "G_2") (pintype "passive"))
      (node (ref "SR7") (pin "15") (pinfunction "QA_15") (pintype "tri_state"))
    )
    (net (code "19") (name "/COLNGATE19") (class "Default")
      (node (ref "COL19.") (pin "2") (pinfunction "G_2") (pintype "passive"))
      (node (ref "SR7") (pin "2") (pinfunction "QC_2") (pintype "tri_state"))
    )
    (net (code "20") (name "/COLNGATE20") (class "Default")
      (node (ref "COL20.") (pin "2") (pinfunction "G_2") (pintype "passive"))
      (node (ref "SR7") (pin "4") (pinfunction "QE_4") (pintype "tri_state"))
    )
    (net (code "21") (name "/COLNGATE21") (class "Default")
      (node (ref "COL21.") (pin "2") (pinfunction "G_2") (pintype "passive"))
      (node (ref "SR7") (pin "6") (pinfunction "QG_6") (pintype "tri_state"))
    )
    (net (code "22") (name "/COLNGATE22") (class "Default")
      (node (ref "COL22.") (pin "2") (pinfunction "G_2") (pintype "passive"))
      (node (ref "SR8") (pin "15") (pinfunction "QA_15") (pintype "tri_state"))
    )
    (net (code "23") (name "/COLNGATE23") (class "Default")
      (node (ref "COL23.") (pin "2") (pinfunction "G_2") (pintype "passive"))
      (node (ref "SR8") (pin "2") (pinfunction "QC_2") (pintype "tri_state"))
    )
    (net (code "24") (name "/COLNGATE24") (class "Default")
      (node (ref "COL24.") (pin "2") (pinfunction "G_2") (pintype "passive"))
      (node (ref "SR8") (pin "4") (pinfunction "QE_4") (pintype "tri_state"))
    )
    (net (code "25") (name "/COLNGATE25") (class "Default")
      (node (ref "COL25.") (pin "2") (pinfunction "G_2") (pintype "passive"))
      (node (ref "SR8") (pin "6") (pinfunction "QG_6") (pintype "tri_state"))
    )
    (net (code "26") (name "/COLNGATE26") (class "Default")
      (node (ref "COL26.") (pin "2") (pinfunction "G_2") (pintype "passive"))
      (node (ref "SR9") (pin "15") (pinfunction "QA_15") (pintype "tri_state"))
    )
    (net (code "27") (name "/COLNGATE27") (class "Default")
      (node (ref "COL27.") (pin "2") (pinfunction "G_2") (pintype "passive"))
      (node (ref "SR9") (pin "2") (pinfunction "QC_2") (pintype "tri_state"))
    )
    (net (code "28") (name "/COLNGATE28") (class "Default")
      (node (ref "COL28.") (pin "2") (pinfunction "G_2") (pintype "passive"))
      (node (ref "SR9") (pin "4") (pinfunction "QE_4") (pintype "tri_state"))
    )
    (net (code "29") (name "/COLNGATE29") (class "Default")
      (node (ref "COL29.") (pin "2") (pinfunction "G_2") (pintype "passive"))
      (node (ref "SR9") (pin "6") (pinfunction "QG_6") (pintype "tri_state"))
    )
    (net (code "30") (name "/COLNGATE30") (class "Default")
      (node (ref "COL30.") (pin "2") (pinfunction "G_2") (pintype "passive"))
      (node (ref "SR10") (pin "15") (pinfunction "QA_15") (pintype "tri_state"))
    )
    (net (code "31") (name "/COLNGATE31") (class "Default")
      (node (ref "COL31.") (pin "2") (pinfunction "G_2") (pintype "passive"))
      (node (ref "SR10") (pin "2") (pinfunction "QC_2") (pintype "tri_state"))
    )
    (net (code "32") (name "/COLNGATE32") (class "Default")
      (node (ref "COL32.") (pin "2") (pinfunction "G_2") (pintype "passive"))
      (node (ref "SR10") (pin "4") (pinfunction "QE_4") (pintype "tri_state"))
    )
    (net (code "33") (name "/COLNGATE33") (class "Default")
      (node (ref "COL33.") (pin "2") (pinfunction "G_2") (pintype "passive"))
      (node (ref "SR10") (pin "6") (pinfunction "QG_6") (pintype "tri_state"))
    )
    (net (code "34") (name "/COLNGATE34") (class "Default")
      (node (ref "COL34.") (pin "2") (pinfunction "G_2") (pintype "passive"))
      (node (ref "SR11") (pin "15") (pinfunction "QA_15") (pintype "tri_state"))
    )
    (net (code "35") (name "/COLNGATE35") (class "Default")
      (node (ref "COL35.") (pin "2") (pinfunction "G_2") (pintype "passive"))
      (node (ref "SR11") (pin "2") (pinfunction "QC_2") (pintype "tri_state"))
    )
    (net (code "36") (name "/COLNGATE36") (class "Default")
      (node (ref "COL36.") (pin "2") (pinfunction "G_2") (pintype "passive"))
      (node (ref "SR11") (pin "4") (pinfunction "QE_4") (pintype "tri_state"))
    )
    (net (code "37") (name "/COLNGATE37") (class "Default")
      (node (ref "COL37.") (pin "2") (pinfunction "G_2") (pintype "passive"))
      (node (ref "SR11") (pin "6") (pinfunction "QG_6") (pintype "tri_state"))
    )
    (net (code "38") (name "/COLNGATE38") (class "Default")
      (node (ref "COL38.") (pin "2") (pinfunction "G_2") (pintype "passive"))
      (node (ref "SR12") (pin "15") (pinfunction "QA_15") (pintype "tri_state"))
    )
    (net (code "39") (name "/COLNGATE39") (class "Default")
      (node (ref "COL39.") (pin "2") (pinfunction "G_2") (pintype "passive"))
      (node (ref "SR12") (pin "2") (pinfunction "QC_2") (pintype "tri_state"))
    )
    (net (code "40") (name "/COLNGATE40") (class "Default")
      (node (ref "COL40.") (pin "2") (pinfunction "G_2") (pintype "passive"))
      (node (ref "SR12") (pin "4") (pinfunction "QE_4") (pintype "tri_state"))
    )
    (net (code "41") (name "/COLNGATE41") (class "Default")
      (node (ref "COL41.") (pin "2") (pinfunction "G_2") (pintype "passive"))
      (node (ref "SR12") (pin "6") (pinfunction "QG_6") (pintype "tri_state"))
    )
    (net (code "42") (name "/COLNGATE42") (class "Default")
      (node (ref "COL42.") (pin "2") (pinfunction "G_2") (pintype "passive"))
      (node (ref "SR13") (pin "15") (pinfunction "QA_15") (pintype "tri_state"))
    )
    (net (code "43") (name "/COLNGATE43") (class "Default")
      (node (ref "COL43.") (pin "2") (pinfunction "G_2") (pintype "passive"))
      (node (ref "SR13") (pin "2") (pinfunction "QC_2") (pintype "tri_state"))
    )
    (net (code "44") (name "/COLNGATE44") (class "Default")
      (node (ref "COL44.") (pin "2") (pinfunction "G_2") (pintype "passive"))
      (node (ref "SR13") (pin "4") (pinfunction "QE_4") (pintype "tri_state"))
    )
    (net (code "45") (name "/COLNGATE45") (class "Default")
      (node (ref "COL45.") (pin "2") (pinfunction "G_2") (pintype "passive"))
      (node (ref "SR13") (pin "6") (pinfunction "QG_6") (pintype "tri_state"))
    )
    (net (code "46") (name "/COLPGATE1") (class "Default")
      (node (ref "COL1.") (pin "4") (pinfunction "G_4") (pintype "passive"))
      (node (ref "SR2") (pin "7") (pinfunction "QH_7") (pintype "tri_state"))
    )
    (net (code "47") (name "/COLPGATE2") (class "Default")
      (node (ref "COL2.") (pin "4") (pinfunction "G_4") (pintype "passive"))
      (node (ref "SR3") (pin "1") (pinfunction "QB_1") (pintype "tri_state"))
    )
    (net (code "48") (name "/COLPGATE3") (class "Default")
      (node (ref "COL3.") (pin "4") (pinfunction "G_4") (pintype "passive"))
      (node (ref "SR3") (pin "3") (pinfunction "QD_3") (pintype "tri_state"))
    )
    (net (code "49") (name "/COLPGATE4") (class "Default")
      (node (ref "COL4.") (pin "4") (pinfunction "G_4") (pintype "passive"))
      (node (ref "SR3") (pin "5") (pinfunction "QF_5") (pintype "tri_state"))
    )
    (net (code "50") (name "/COLPGATE5") (class "Default")
      (node (ref "COL5.") (pin "4") (pinfunction "G_4") (pintype "passive"))
      (node (ref "SR3") (pin "7") (pinfunction "QH_7") (pintype "tri_state"))
    )
    (net (code "51") (name "/COLPGATE6") (class "Default")
      (node (ref "COL6.") (pin "4") (pinfunction "G_4") (pintype "passive"))
      (node (ref "SR4") (pin "1") (pinfunction "QB_1") (pintype "tri_state"))
    )
    (net (code "52") (name "/COLPGATE7") (class "Default")
      (node (ref "COL7.") (pin "4") (pinfunction "G_4") (pintype "passive"))
      (node (ref "SR4") (pin "3") (pinfunction "QD_3") (pintype "tri_state"))
    )
    (net (code "53") (name "/COLPGATE8") (class "Default")
      (node (ref "COL8.") (pin "4") (pinfunction "G_4") (pintype "passive"))
      (node (ref "SR4") (pin "5") (pinfunction "QF_5") (pintype "tri_state"))
    )
    (net (code "54") (name "/COLPGATE9") (class "Default")
      (node (ref "COL9.") (pin "4") (pinfunction "G_4") (pintype "passive"))
      (node (ref "SR4") (pin "7") (pinfunction "QH_7") (pintype "tri_state"))
    )
    (net (code "55") (name "/COLPGATE10") (class "Default")
      (node (ref "COL10.") (pin "4") (pinfunction "G_4") (pintype "passive"))
      (node (ref "SR5") (pin "1") (pinfunction "QB_1") (pintype "tri_state"))
    )
    (net (code "56") (name "/COLPGATE11") (class "Default")
      (node (ref "COL11.") (pin "4") (pinfunction "G_4") (pintype "passive"))
      (node (ref "SR5") (pin "3") (pinfunction "QD_3") (pintype "tri_state"))
    )
    (net (code "57") (name "/COLPGATE12") (class "Default")
      (node (ref "COL12.") (pin "4") (pinfunction "G_4") (pintype "passive"))
      (node (ref "SR5") (pin "5") (pinfunction "QF_5") (pintype "tri_state"))
    )
    (net (code "58") (name "/COLPGATE13") (class "Default")
      (node (ref "COL13.") (pin "4") (pinfunction "G_4") (pintype "passive"))
      (node (ref "SR5") (pin "7") (pinfunction "QH_7") (pintype "tri_state"))
    )
    (net (code "59") (name "/COLPGATE14") (class "Default")
      (node (ref "COL14.") (pin "4") (pinfunction "G_4") (pintype "passive"))
      (node (ref "SR6") (pin "1") (pinfunction "QB_1") (pintype "tri_state"))
    )
    (net (code "60") (name "/COLPGATE15") (class "Default")
      (node (ref "COL15.") (pin "4") (pinfunction "G_4") (pintype "passive"))
      (node (ref "SR6") (pin "3") (pinfunction "QD_3") (pintype "tri_state"))
    )
    (net (code "61") (name "/COLPGATE16") (class "Default")
      (node (ref "COL16.") (pin "4") (pinfunction "G_4") (pintype "passive"))
      (node (ref "SR6") (pin "5") (pinfunction "QF_5") (pintype "tri_state"))
    )
    (net (code "62") (name "/COLPGATE17") (class "Default")
      (node (ref "COL17.") (pin "4") (pinfunction "G_4") (pintype "passive"))
      (node (ref "SR6") (pin "7") (pinfunction "QH_7") (pintype "tri_state"))
    )
    (net (code "63") (name "/COLPGATE18") (class "Default")
      (node (ref "COL18.") (pin "4") (pinfunction "G_4") (pintype "passive"))
      (node (ref "SR7") (pin "1") (pinfunction "QB_1") (pintype "tri_state"))
    )
    (net (code "64") (name "/COLPGATE19") (class "Default")
      (node (ref "COL19.") (pin "4") (pinfunction "G_4") (pintype "passive"))
      (node (ref "SR7") (pin "3") (pinfunction "QD_3") (pintype "tri_state"))
    )
    (net (code "65") (name "/COLPGATE20") (class "Default")
      (node (ref "COL20.") (pin "4") (pinfunction "G_4") (pintype "passive"))
      (node (ref "SR7") (pin "5") (pinfunction "QF_5") (pintype "tri_state"))
    )
    (net (code "66") (name "/COLPGATE21") (class "Default")
      (node (ref "COL21.") (pin "4") (pinfunction "G_4") (pintype "passive"))
      (node (ref "SR7") (pin "7") (pinfunction "QH_7") (pintype "tri_state"))
    )
    (net (code "67") (name "/COLPGATE22") (class "Default")
      (node (ref "COL22.") (pin "4") (pinfunction "G_4") (pintype "passive"))
      (node (ref "SR8") (pin "1") (pinfunction "QB_1") (pintype "tri_state"))
    )
    (net (code "68") (name "/COLPGATE23") (class "Default")
      (node (ref "COL23.") (pin "4") (pinfunction "G_4") (pintype "passive"))
      (node (ref "SR8") (pin "3") (pinfunction "QD_3") (pintype "tri_state"))
    )
    (net (code "69") (name "/COLPGATE24") (class "Default")
      (node (ref "COL24.") (pin "4") (pinfunction "G_4") (pintype "passive"))
      (node (ref "SR8") (pin "5") (pinfunction "QF_5") (pintype "tri_state"))
    )
    (net (code "70") (name "/COLPGATE25") (class "Default")
      (node (ref "COL25.") (pin "4") (pinfunction "G_4") (pintype "passive"))
      (node (ref "SR8") (pin "7") (pinfunction "QH_7") (pintype "tri_state"))
    )
    (net (code "71") (name "/COLPGATE26") (class "Default")
      (node (ref "COL26.") (pin "4") (pinfunction "G_4") (pintype "passive"))
      (node (ref "SR9") (pin "1") (pinfunction "QB_1") (pintype "tri_state"))
    )
    (net (code "72") (name "/COLPGATE27") (class "Default")
      (node (ref "COL27.") (pin "4") (pinfunction "G_4") (pintype "passive"))
      (node (ref "SR9") (pin "3") (pinfunction "QD_3") (pintype "tri_state"))
    )
    (net (code "73") (name "/COLPGATE28") (class "Default")
      (node (ref "COL28.") (pin "4") (pinfunction "G_4") (pintype "passive"))
      (node (ref "SR9") (pin "5") (pinfunction "QF_5") (pintype "tri_state"))
    )
    (net (code "74") (name "/COLPGATE29") (class "Default")
      (node (ref "COL29.") (pin "4") (pinfunction "G_4") (pintype "passive"))
      (node (ref "SR9") (pin "7") (pinfunction "QH_7") (pintype "tri_state"))
    )
    (net (code "75") (name "/COLPGATE30") (class "Default")
      (node (ref "COL30.") (pin "4") (pinfunction "G_4") (pintype "passive"))
      (node (ref "SR10") (pin "1") (pinfunction "QB_1") (pintype "tri_state"))
    )
    (net (code "76") (name "/COLPGATE31") (class "Default")
      (node (ref "COL31.") (pin "4") (pinfunction "G_4") (pintype "passive"))
      (node (ref "SR10") (pin "3") (pinfunction "QD_3") (pintype "tri_state"))
    )
    (net (code "77") (name "/COLPGATE32") (class "Default")
      (node (ref "COL32.") (pin "4") (pinfunction "G_4") (pintype "passive"))
      (node (ref "SR10") (pin "5") (pinfunction "QF_5") (pintype "tri_state"))
    )
    (net (code "78") (name "/COLPGATE33") (class "Default")
      (node (ref "COL33.") (pin "4") (pinfunction "G_4") (pintype "passive"))
      (node (ref "SR10") (pin "7") (pinfunction "QH_7") (pintype "tri_state"))
    )
    (net (code "79") (name "/COLPGATE34") (class "Default")
      (node (ref "COL34.") (pin "4") (pinfunction "G_4") (pintype "passive"))
      (node (ref "SR11") (pin "1") (pinfunction "QB_1") (pintype "tri_state"))
    )
    (net (code "80") (name "/COLPGATE35") (class "Default")
      (node (ref "COL35.") (pin "4") (pinfunction "G_4") (pintype "passive"))
      (node (ref "SR11") (pin "3") (pinfunction "QD_3") (pintype "tri_state"))
    )
    (net (code "81") (name "/COLPGATE36") (class "Default")
      (node (ref "COL36.") (pin "4") (pinfunction "G_4") (pintype "passive"))
      (node (ref "SR11") (pin "5") (pinfunction "QF_5") (pintype "tri_state"))
    )
    (net (code "82") (name "/COLPGATE37") (class "Default")
      (node (ref "COL37.") (pin "4") (pinfunction "G_4") (pintype "passive"))
      (node (ref "SR11") (pin "7") (pinfunction "QH_7") (pintype "tri_state"))
    )
    (net (code "83") (name "/COLPGATE38") (class "Default")
      (node (ref "COL38.") (pin "4") (pinfunction "G_4") (pintype "passive"))
      (node (ref "SR12") (pin "1") (pinfunction "QB_1") (pintype "tri_state"))
    )
    (net (code "84") (name "/COLPGATE39") (class "Default")
      (node (ref "COL39.") (pin "4") (pinfunction "G_4") (pintype "passive"))
      (node (ref "SR12") (pin "3") (pinfunction "QD_3") (pintype "tri_state"))
    )
    (net (code "85") (name "/COLPGATE40") (class "Default")
      (node (ref "COL40.") (pin "4") (pinfunction "G_4") (pintype "passive"))
      (node (ref "SR12") (pin "5") (pinfunction "QF_5") (pintype "tri_state"))
    )
    (net (code "86") (name "/COLPGATE41") (class "Default")
      (node (ref "COL41.") (pin "4") (pinfunction "G_4") (pintype "passive"))
      (node (ref "SR12") (pin "7") (pinfunction "QH_7") (pintype "tri_state"))
    )
    (net (code "87") (name "/COLPGATE42") (class "Default")
      (node (ref "COL42.") (pin "4") (pinfunction "G_4") (pintype "passive"))
      (node (ref "SR13") (pin "1") (pinfunction "QB_1") (pintype "tri_state"))
    )
    (net (code "88") (name "/COLPGATE43") (class "Default")
      (node (ref "COL43.") (pin "4") (pinfunction "G_4") (pintype "passive"))
      (node (ref "SR13") (pin "3") (pinfunction "QD_3") (pintype "tri_state"))
    )
    (net (code "89") (name "/COLPGATE44") (class "Default")
      (node (ref "COL44.") (pin "4") (pinfunction "G_4") (pintype "passive"))
      (node (ref "SR13") (pin "5") (pinfunction "QF_5") (pintype "tri_state"))
    )
    (net (code "90") (name "/COLPGATE45") (class "Default")
      (node (ref "COL45.") (pin "4") (pinfunction "G_4") (pintype "passive"))
      (node (ref "SR13") (pin "7") (pinfunction "QH_7") (pintype "tri_state"))
    )
    (net (code "91") (name "/FLIPVOLTPOSITIVE") (class "Default")
      (node (ref "COL1.") (pin "3") (pinfunction "S_3") (pintype "passive"))
      (node (ref "COL10.") (pin "3") (pinfunction "S_3") (pintype "passive"))
      (node (ref "COL11.") (pin "3") (pinfunction "S_3") (pintype "passive"))
      (node (ref "COL12.") (pin "3") (pinfunction "S_3") (pintype "passive"))
      (node (ref "COL13.") (pin "3") (pinfunction "S_3") (pintype "passive"))
      (node (ref "COL14.") (pin "3") (pinfunction "S_3") (pintype "passive"))
      (node (ref "COL15.") (pin "3") (pinfunction "S_3") (pintype "passive"))
      (node (ref "COL16.") (pin "3") (pinfunction "S_3") (pintype "passive"))
      (node (ref "COL17.") (pin "3") (pinfunction "S_3") (pintype "passive"))
      (node (ref "COL18.") (pin "3") (pinfunction "S_3") (pintype "passive"))
      (node (ref "COL19.") (pin "3") (pinfunction "S_3") (pintype "passive"))
      (node (ref "COL2.") (pin "3") (pinfunction "S_3") (pintype "passive"))
      (node (ref "COL20.") (pin "3") (pinfunction "S_3") (pintype "passive"))
      (node (ref "COL21.") (pin "3") (pinfunction "S_3") (pintype "passive"))
      (node (ref "COL22.") (pin "3") (pinfunction "S_3") (pintype "passive"))
      (node (ref "COL23.") (pin "3") (pinfunction "S_3") (pintype "passive"))
      (node (ref "COL24.") (pin "3") (pinfunction "S_3") (pintype "passive"))
      (node (ref "COL25.") (pin "3") (pinfunction "S_3") (pintype "passive"))
      (node (ref "COL26.") (pin "3") (pinfunction "S_3") (pintype "passive"))
      (node (ref "COL27.") (pin "3") (pinfunction "S_3") (pintype "passive"))
      (node (ref "COL28.") (pin "3") (pinfunction "S_3") (pintype "passive"))
      (node (ref "COL29.") (pin "3") (pinfunction "S_3") (pintype "passive"))
      (node (ref "COL3.") (pin "3") (pinfunction "S_3") (pintype "passive"))
      (node (ref "COL30.") (pin "3") (pinfunction "S_3") (pintype "passive"))
      (node (ref "COL31.") (pin "3") (pinfunction "S_3") (pintype "passive"))
      (node (ref "COL32.") (pin "3") (pinfunction "S_3") (pintype "passive"))
      (node (ref "COL33.") (pin "3") (pinfunction "S_3") (pintype "passive"))
      (node (ref "COL34.") (pin "3") (pinfunction "S_3") (pintype "passive"))
      (node (ref "COL35.") (pin "3") (pinfunction "S_3") (pintype "passive"))
      (node (ref "COL36.") (pin "3") (pinfunction "S_3") (pintype "passive"))
      (node (ref "COL37.") (pin "3") (pinfunction "S_3") (pintype "passive"))
      (node (ref "COL38.") (pin "3") (pinfunction "S_3") (pintype "passive"))
      (node (ref "COL39.") (pin "3") (pinfunction "S_3") (pintype "passive"))
      (node (ref "COL4.") (pin "3") (pinfunction "S_3") (pintype "passive"))
      (node (ref "COL40.") (pin "3") (pinfunction "S_3") (pintype "passive"))
      (node (ref "COL41.") (pin "3") (pinfunction "S_3") (pintype "passive"))
      (node (ref "COL42.") (pin "3") (pinfunction "S_3") (pintype "passive"))
      (node (ref "COL43.") (pin "3") (pinfunction "S_3") (pintype "passive"))
      (node (ref "COL44.") (pin "3") (pinfunction "S_3") (pintype "passive"))
      (node (ref "COL45.") (pin "3") (pinfunction "S_3") (pintype "passive"))
      (node (ref "COL5.") (pin "3") (pinfunction "S_3") (pintype "passive"))
      (node (ref "COL6.") (pin "3") (pinfunction "S_3") (pintype "passive"))
      (node (ref "COL7.") (pin "3") (pinfunction "S_3") (pintype "passive"))
      (node (ref "COL8.") (pin "3") (pinfunction "S_3") (pintype "passive"))
      (node (ref "COL9.") (pin "3") (pinfunction "S_3") (pintype "passive"))
      (node (ref "FLIPCAP") (pin "+") (pinfunction "+_+") (pintype "passive"))
      (node (ref "JP1") (pin "3") (pinfunction "3_3") (pintype "passive"))
      (node (ref "R10") (pin "2") (pinfunction "2_2") (pintype "passive"))
      (node (ref "R12") (pin "2") (pinfunction "2_2") (pintype "passive"))
      (node (ref "R14") (pin "2") (pinfunction "2_2") (pintype "passive"))
      (node (ref "R2") (pin "2") (pinfunction "2_2") (pintype "passive"))
      (node (ref "R4") (pin "2") (pinfunction "2_2") (pintype "passive"))
      (node (ref "R6") (pin "2") (pinfunction "2_2") (pintype "passive"))
      (node (ref "R8") (pin "2") (pinfunction "2_2") (pintype "passive"))
      (node (ref "ROW1.") (pin "3") (pinfunction "S_3") (pintype "passive"))
      (node (ref "ROW2.") (pin "3") (pinfunction "S_3") (pintype "passive"))
      (node (ref "ROW3.") (pin "3") (pinfunction "S_3") (pintype "passive"))
      (node (ref "ROW4.") (pin "3") (pinfunction "S_3") (pintype "passive"))
      (node (ref "ROW5.") (pin "3") (pinfunction "S_3") (pintype "passive"))
      (node (ref "ROW6.") (pin "3") (pinfunction "S_3") (pintype "passive"))
      (node (ref "ROW7.") (pin "3") (pinfunction "S_3") (pintype "passive"))
    )
    (net (code "92") (name "/LEDPOS") (class "Default")
      (node (ref "JP1") (pin "4") (pinfunction "4_4") (pintype "passive"))
      (node (ref "X1") (pin "A2") (pinfunction "A2_A2") (pintype "passive"))
      (node (ref "X1") (pin "C2") (pinfunction "C2_C2") (pintype "passive"))
    )
    (net (code "93") (name "/RCK") (class "Default")
      (node (ref "JP1") (pin "5") (pinfunction "5_5") (pintype "passive"))
      (node (ref "SR1") (pin "12") (pinfunction "RCK_12") (pintype "input"))
      (node (ref "SR10") (pin "12") (pinfunction "RCK_12") (pintype "input"))
      (node (ref "SR11") (pin "12") (pinfunction "RCK_12") (pintype "input"))
      (node (ref "SR12") (pin "12") (pinfunction "RCK_12") (pintype "input"))
      (node (ref "SR13") (pin "12") (pinfunction "RCK_12") (pintype "input"))
      (node (ref "SR2") (pin "12") (pinfunction "RCK_12") (pintype "input"))
      (node (ref "SR3") (pin "12") (pinfunction "RCK_12") (pintype "input"))
      (node (ref "SR4") (pin "12") (pinfunction "RCK_12") (pintype "input"))
      (node (ref "SR5") (pin "12") (pinfunction "RCK_12") (pintype "input"))
      (node (ref "SR6") (pin "12") (pinfunction "RCK_12") (pintype "input"))
      (node (ref "SR7") (pin "12") (pinfunction "RCK_12") (pintype "input"))
      (node (ref "SR8") (pin "12") (pinfunction "RCK_12") (pintype "input"))
      (node (ref "SR9") (pin "12") (pinfunction "RCK_12") (pintype "input"))
    )
    (net (code "94") (name "/ROWNGATE1") (class "Default")
      (node (ref "R1") (pin "2") (pinfunction "2_2") (pintype "passive"))
      (node (ref "ROW1.") (pin "2") (pinfunction "G_2") (pintype "passive"))
      (node (ref "SR1") (pin "15") (pinfunction "QA_15") (pintype "tri_state"))
    )
    (net (code "95") (name "/ROWNGATE2") (class "Default")
      (node (ref "R3") (pin "2") (pinfunction "2_2") (pintype "passive"))
      (node (ref "ROW2.") (pin "2") (pinfunction "G_2") (pintype "passive"))
      (node (ref "SR1") (pin "2") (pinfunction "QC_2") (pintype "tri_state"))
    )
    (net (code "96") (name "/ROWNGATE3") (class "Default")
      (node (ref "R5") (pin "2") (pinfunction "2_2") (pintype "passive"))
      (node (ref "ROW3.") (pin "2") (pinfunction "G_2") (pintype "passive"))
      (node (ref "SR1") (pin "4") (pinfunction "QE_4") (pintype "tri_state"))
    )
    (net (code "97") (name "/ROWNGATE4") (class "Default")
      (node (ref "R7") (pin "2") (pinfunction "2_2") (pintype "passive"))
      (node (ref "ROW4.") (pin "2") (pinfunction "G_2") (pintype "passive"))
      (node (ref "SR1") (pin "6") (pinfunction "QG_6") (pintype "tri_state"))
    )
    (net (code "98") (name "/ROWNGATE5") (class "Default")
      (node (ref "R9") (pin "2") (pinfunction "2_2") (pintype "passive"))
      (node (ref "ROW5.") (pin "2") (pinfunction "G_2") (pintype "passive"))
      (node (ref "SR2") (pin "15") (pinfunction "QA_15") (pintype "tri_state"))
    )
    (net (code "99") (name "/ROWNGATE6") (class "Default")
      (node (ref "R11") (pin "2") (pinfunction "2_2") (pintype "passive"))
      (node (ref "ROW6.") (pin "2") (pinfunction "G_2") (pintype "passive"))
      (node (ref "SR2") (pin "2") (pinfunction "QC_2") (pintype "tri_state"))
    )
    (net (code "100") (name "/ROWNGATE7") (class "Default")
      (node (ref "R13") (pin "2") (pinfunction "2_2") (pintype "passive"))
      (node (ref "ROW7.") (pin "2") (pinfunction "G_2") (pintype "passive"))
      (node (ref "SR2") (pin "4") (pinfunction "QE_4") (pintype "tri_state"))
    )
    (net (code "101") (name "/ROWPGATE1") (class "Default")
      (node (ref "R2") (pin "1") (pinfunction "1_1") (pintype "passive"))
      (node (ref "ROW1.") (pin "4") (pinfunction "G_4") (pintype "passive"))
      (node (ref "SR1") (pin "1") (pinfunction "QB_1") (pintype "tri_state"))
    )
    (net (code "102") (name "/ROWPGATE2") (class "Default")
      (node (ref "R4") (pin "1") (pinfunction "1_1") (pintype "passive"))
      (node (ref "ROW2.") (pin "4") (pinfunction "G_4") (pintype "passive"))
      (node (ref "SR1") (pin "3") (pinfunction "QD_3") (pintype "tri_state"))
    )
    (net (code "103") (name "/ROWPGATE3") (class "Default")
      (node (ref "R6") (pin "1") (pinfunction "1_1") (pintype "passive"))
      (node (ref "ROW3.") (pin "4") (pinfunction "G_4") (pintype "passive"))
      (node (ref "SR1") (pin "5") (pinfunction "QF_5") (pintype "tri_state"))
    )
    (net (code "104") (name "/ROWPGATE4") (class "Default")
      (node (ref "R8") (pin "1") (pinfunction "1_1") (pintype "passive"))
      (node (ref "ROW4.") (pin "4") (pinfunction "G_4") (pintype "passive"))
      (node (ref "SR1") (pin "7") (pinfunction "QH_7") (pintype "tri_state"))
    )
    (net (code "105") (name "/ROWPGATE5") (class "Default")
      (node (ref "R10") (pin "1") (pinfunction "1_1") (pintype "passive"))
      (node (ref "ROW5.") (pin "4") (pinfunction "G_4") (pintype "passive"))
      (node (ref "SR2") (pin "1") (pinfunction "QB_1") (pintype "tri_state"))
    )
    (net (code "106") (name "/ROWPGATE6") (class "Default")
      (node (ref "R12") (pin "1") (pinfunction "1_1") (pintype "passive"))
      (node (ref "ROW6.") (pin "4") (pinfunction "G_4") (pintype "passive"))
      (node (ref "SR2") (pin "3") (pinfunction "QD_3") (pintype "tri_state"))
    )
    (net (code "107") (name "/ROWPGATE7") (class "Default")
      (node (ref "R14") (pin "1") (pinfunction "1_1") (pintype "passive"))
      (node (ref "ROW7.") (pin "4") (pinfunction "G_4") (pintype "passive"))
      (node (ref "SR2") (pin "5") (pinfunction "QF_5") (pintype "tri_state"))
    )
    (net (code "108") (name "/SCK") (class "Default")
      (node (ref "JP1") (pin "6") (pinfunction "6_6") (pintype "passive"))
      (node (ref "SR1") (pin "11") (pinfunction "SCK_11") (pintype "input"))
      (node (ref "SR10") (pin "11") (pinfunction "SCK_11") (pintype "input"))
      (node (ref "SR11") (pin "11") (pinfunction "SCK_11") (pintype "input"))
      (node (ref "SR12") (pin "11") (pinfunction "SCK_11") (pintype "input"))
      (node (ref "SR13") (pin "11") (pinfunction "SCK_11") (pintype "input"))
      (node (ref "SR2") (pin "11") (pinfunction "SCK_11") (pintype "input"))
      (node (ref "SR3") (pin "11") (pinfunction "SCK_11") (pintype "input"))
      (node (ref "SR4") (pin "11") (pinfunction "SCK_11") (pintype "input"))
      (node (ref "SR5") (pin "11") (pinfunction "SCK_11") (pintype "input"))
      (node (ref "SR6") (pin "11") (pinfunction "SCK_11") (pintype "input"))
      (node (ref "SR7") (pin "11") (pinfunction "SCK_11") (pintype "input"))
      (node (ref "SR8") (pin "11") (pinfunction "SCK_11") (pintype "input"))
      (node (ref "SR9") (pin "11") (pinfunction "SCK_11") (pintype "input"))
    )
    (net (code "109") (name "GND") (class "Default")
      (node (ref "C1") (pin "2") (pinfunction "2_2") (pintype "passive"))
      (node (ref "C10") (pin "2") (pinfunction "2_2") (pintype "passive"))
      (node (ref "C11") (pin "2") (pinfunction "2_2") (pintype "passive"))
      (node (ref "C12") (pin "2") (pinfunction "2_2") (pintype "passive"))
      (node (ref "C13") (pin "2") (pinfunction "2_2") (pintype "passive"))
      (node (ref "C2") (pin "2") (pinfunction "2_2") (pintype "passive"))
      (node (ref "C3") (pin "2") (pinfunction "2_2") (pintype "passive"))
      (node (ref "C4") (pin "2") (pinfunction "2_2") (pintype "passive"))
      (node (ref "C5") (pin "2") (pinfunction "2_2") (pintype "passive"))
      (node (ref "C6") (pin "2") (pinfunction "2_2") (pintype "passive"))
      (node (ref "C7") (pin "2") (pinfunction "2_2") (pintype "passive"))
      (node (ref "C8") (pin "2") (pinfunction "2_2") (pintype "passive"))
      (node (ref "C9") (pin "2") (pinfunction "2_2") (pintype "passive"))
      (node (ref "COL1.") (pin "1") (pinfunction "S_1") (pintype "passive"))
      (node (ref "COL10.") (pin "1") (pinfunction "S_1") (pintype "passive"))
      (node (ref "COL11.") (pin "1") (pinfunction "S_1") (pintype "passive"))
      (node (ref "COL12.") (pin "1") (pinfunction "S_1") (pintype "passive"))
      (node (ref "COL13.") (pin "1") (pinfunction "S_1") (pintype "passive"))
      (node (ref "COL14.") (pin "1") (pinfunction "S_1") (pintype "passive"))
      (node (ref "COL15.") (pin "1") (pinfunction "S_1") (pintype "passive"))
      (node (ref "COL16.") (pin "1") (pinfunction "S_1") (pintype "passive"))
      (node (ref "COL17.") (pin "1") (pinfunction "S_1") (pintype "passive"))
      (node (ref "COL18.") (pin "1") (pinfunction "S_1") (pintype "passive"))
      (node (ref "COL19.") (pin "1") (pinfunction "S_1") (pintype "passive"))
      (node (ref "COL2.") (pin "1") (pinfunction "S_1") (pintype "passive"))
      (node (ref "COL20.") (pin "1") (pinfunction "S_1") (pintype "passive"))
      (node (ref "COL21.") (pin "1") (pinfunction "S_1") (pintype "passive"))
      (node (ref "COL22.") (pin "1") (pinfunction "S_1") (pintype "passive"))
      (node (ref "COL23.") (pin "1") (pinfunction "S_1") (pintype "passive"))
      (node (ref "COL24.") (pin "1") (pinfunction "S_1") (pintype "passive"))
      (node (ref "COL25.") (pin "1") (pinfunction "S_1") (pintype "passive"))
      (node (ref "COL26.") (pin "1") (pinfunction "S_1") (pintype "passive"))
      (node (ref "COL27.") (pin "1") (pinfunction "S_1") (pintype "passive"))
      (node (ref "COL28.") (pin "1") (pinfunction "S_1") (pintype "passive"))
      (node (ref "COL29.") (pin "1") (pinfunction "S_1") (pintype "passive"))
      (node (ref "COL3.") (pin "1") (pinfunction "S_1") (pintype "passive"))
      (node (ref "COL30.") (pin "1") (pinfunction "S_1") (pintype "passive"))
      (node (ref "COL31.") (pin "1") (pinfunction "S_1") (pintype "passive"))
      (node (ref "COL32.") (pin "1") (pinfunction "S_1") (pintype "passive"))
      (node (ref "COL33.") (pin "1") (pinfunction "S_1") (pintype "passive"))
      (node (ref "COL34.") (pin "1") (pinfunction "S_1") (pintype "passive"))
      (node (ref "COL35.") (pin "1") (pinfunction "S_1") (pintype "passive"))
      (node (ref "COL36.") (pin "1") (pinfunction "S_1") (pintype "passive"))
      (node (ref "COL37.") (pin "1") (pinfunction "S_1") (pintype "passive"))
      (node (ref "COL38.") (pin "1") (pinfunction "S_1") (pintype "passive"))
      (node (ref "COL39.") (pin "1") (pinfunction "S_1") (pintype "passive"))
      (node (ref "COL4.") (pin "1") (pinfunction "S_1") (pintype "passive"))
      (node (ref "COL40.") (pin "1") (pinfunction "S_1") (pintype "passive"))
      (node (ref "COL41.") (pin "1") (pinfunction "S_1") (pintype "passive"))
      (node (ref "COL42.") (pin "1") (pinfunction "S_1") (pintype "passive"))
      (node (ref "COL43.") (pin "1") (pinfunction "S_1") (pintype "passive"))
      (node (ref "COL44.") (pin "1") (pinfunction "S_1") (pintype "passive"))
      (node (ref "COL45.") (pin "1") (pinfunction "S_1") (pintype "passive"))
      (node (ref "COL5.") (pin "1") (pinfunction "S_1") (pintype "passive"))
      (node (ref "COL6.") (pin "1") (pinfunction "S_1") (pintype "passive"))
      (node (ref "COL7.") (pin "1") (pinfunction "S_1") (pintype "passive"))
      (node (ref "COL8.") (pin "1") (pinfunction "S_1") (pintype "passive"))
      (node (ref "COL9.") (pin "1") (pinfunction "S_1") (pintype "passive"))
      (node (ref "FLIPCAP") (pin "-") (pinfunction "-_-") (pintype "passive"))
      (node (ref "JP1") (pin "1") (pinfunction "1_1") (pintype "passive"))
      (node (ref "JP1") (pin "8") (pinfunction "8_8") (pintype "passive"))
      (node (ref "LOGICCAP") (pin "-") (pinfunction "-_-") (pintype "passive"))
      (node (ref "R1") (pin "1") (pinfunction "1_1") (pintype "passive"))
      (node (ref "R11") (pin "1") (pinfunction "1_1") (pintype "passive"))
      (node (ref "R13") (pin "1") (pinfunction "1_1") (pintype "passive"))
      (node (ref "R3") (pin "1") (pinfunction "1_1") (pintype "passive"))
      (node (ref "R5") (pin "1") (pinfunction "1_1") (pintype "passive"))
      (node (ref "R7") (pin "1") (pinfunction "1_1") (pintype "passive"))
      (node (ref "R9") (pin "1") (pinfunction "1_1") (pintype "passive"))
      (node (ref "ROW1.") (pin "1") (pinfunction "S_1") (pintype "passive"))
      (node (ref "ROW2.") (pin "1") (pinfunction "S_1") (pintype "passive"))
      (node (ref "ROW3.") (pin "1") (pinfunction "S_1") (pintype "passive"))
      (node (ref "ROW4.") (pin "1") (pinfunction "S_1") (pintype "passive"))
      (node (ref "ROW5.") (pin "1") (pinfunction "S_1") (pintype "passive"))
      (node (ref "ROW6.") (pin "1") (pinfunction "S_1") (pintype "passive"))
      (node (ref "ROW7.") (pin "1") (pinfunction "S_1") (pintype "passive"))
      (node (ref "SR1") (pin "13") (pinfunction "G_13") (pintype "input"))
      (node (ref "SR10") (pin "13") (pinfunction "G_13") (pintype "input"))
      (node (ref "SR11") (pin "13") (pinfunction "G_13") (pintype "input"))
      (node (ref "SR12") (pin "13") (pinfunction "G_13") (pintype "input"))
      (node (ref "SR13") (pin "13") (pinfunction "G_13") (pintype "input"))
      (node (ref "SR2") (pin "13") (pinfunction "G_13") (pintype "input"))
      (node (ref "SR3") (pin "13") (pinfunction "G_13") (pintype "input"))
      (node (ref "SR4") (pin "13") (pinfunction "G_13") (pintype "input"))
      (node (ref "SR5") (pin "13") (pinfunction "G_13") (pintype "input"))
      (node (ref "SR6") (pin "13") (pinfunction "G_13") (pintype "input"))
      (node (ref "SR7") (pin "13") (pinfunction "G_13") (pintype "input"))
      (node (ref "SR8") (pin "13") (pinfunction "G_13") (pintype "input"))
      (node (ref "SR9") (pin "13") (pinfunction "G_13") (pintype "input"))
      (node (ref "X1") (pin "A1") (pinfunction "A1_A1") (pintype "passive"))
      (node (ref "X1") (pin "C1") (pinfunction "C1_C1") (pintype "passive"))
    )
    (net (code "110") (name "Net-(COL1.A-D-Pad7)") (class "Default")
      (node (ref "COL1.") (pin "5") (pinfunction "D_5") (pintype "passive"))
      (node (ref "COL1.") (pin "6") (pinfunction "D_6") (pintype "passive"))
      (node (ref "COL1.") (pin "7") (pinfunction "D_7") (pintype "passive"))
      (node (ref "COL1.") (pin "8") (pinfunction "D_8") (pintype "passive"))
      (node (ref "X1") (pin "C10") (pinfunction "C10_C10") (pintype "passive"))
    )
    (net (code "111") (name "Net-(COL2.A-D-Pad7)") (class "Default")
      (node (ref "COL2.") (pin "5") (pinfunction "D_5") (pintype "passive"))
      (node (ref "COL2.") (pin "6") (pinfunction "D_6") (pintype "passive"))
      (node (ref "COL2.") (pin "7") (pinfunction "D_7") (pintype "passive"))
      (node (ref "COL2.") (pin "8") (pinfunction "D_8") (pintype "passive"))
      (node (ref "X1") (pin "A11") (pinfunction "A11_A11") (pintype "passive"))
    )
    (net (code "112") (name "Net-(COL3.A-D-Pad7)") (class "Default")
      (node (ref "COL3.") (pin "5") (pinfunction "D_5") (pintype "passive"))
      (node (ref "COL3.") (pin "6") (pinfunction "D_6") (pintype "passive"))
      (node (ref "COL3.") (pin "7") (pinfunction "D_7") (pintype "passive"))
      (node (ref "COL3.") (pin "8") (pinfunction "D_8") (pintype "passive"))
      (node (ref "X1") (pin "C11") (pinfunction "C11_C11") (pintype "passive"))
    )
    (net (code "113") (name "Net-(COL4.A-D-Pad7)") (class "Default")
      (node (ref "COL4.") (pin "5") (pinfunction "D_5") (pintype "passive"))
      (node (ref "COL4.") (pin "6") (pinfunction "D_6") (pintype "passive"))
      (node (ref "COL4.") (pin "7") (pinfunction "D_7") (pintype "passive"))
      (node (ref "COL4.") (pin "8") (pinfunction "D_8") (pintype "passive"))
      (node (ref "X1") (pin "A12") (pinfunction "A12_A12") (pintype "passive"))
    )
    (net (code "114") (name "Net-(COL5.A-D-Pad7)") (class "Default")
      (node (ref "COL5.") (pin "5") (pinfunction "D_5") (pintype "passive"))
      (node (ref "COL5.") (pin "6") (pinfunction "D_6") (pintype "passive"))
      (node (ref "COL5.") (pin "7") (pinfunction "D_7") (pintype "passive"))
      (node (ref "COL5.") (pin "8") (pinfunction "D_8") (pintype "passive"))
      (node (ref "X1") (pin "C12") (pinfunction "C12_C12") (pintype "passive"))
    )
    (net (code "115") (name "Net-(COL6.A-D-Pad7)") (class "Default")
      (node (ref "COL6.") (pin "5") (pinfunction "D_5") (pintype "passive"))
      (node (ref "COL6.") (pin "6") (pinfunction "D_6") (pintype "passive"))
      (node (ref "COL6.") (pin "7") (pinfunction "D_7") (pintype "passive"))
      (node (ref "COL6.") (pin "8") (pinfunction "D_8") (pintype "passive"))
      (node (ref "X1") (pin "A13") (pinfunction "A13_A13") (pintype "passive"))
    )
    (net (code "116") (name "Net-(COL7.A-D-Pad7)") (class "Default")
      (node (ref "COL7.") (pin "5") (pinfunction "D_5") (pintype "passive"))
      (node (ref "COL7.") (pin "6") (pinfunction "D_6") (pintype "passive"))
      (node (ref "COL7.") (pin "7") (pinfunction "D_7") (pintype "passive"))
      (node (ref "COL7.") (pin "8") (pinfunction "D_8") (pintype "passive"))
      (node (ref "X1") (pin "C13") (pinfunction "C13_C13") (pintype "passive"))
    )
    (net (code "117") (name "Net-(COL8.A-D-Pad7)") (class "Default")
      (node (ref "COL8.") (pin "5") (pinfunction "D_5") (pintype "passive"))
      (node (ref "COL8.") (pin "6") (pinfunction "D_6") (pintype "passive"))
      (node (ref "COL8.") (pin "7") (pinfunction "D_7") (pintype "passive"))
      (node (ref "COL8.") (pin "8") (pinfunction "D_8") (pintype "passive"))
      (node (ref "X1") (pin "A14") (pinfunction "A14_A14") (pintype "passive"))
    )
    (net (code "118") (name "Net-(COL9.A-D-Pad7)") (class "Default")
      (node (ref "COL9.") (pin "5") (pinfunction "D_5") (pintype "passive"))
      (node (ref "COL9.") (pin "6") (pinfunction "D_6") (pintype "passive"))
      (node (ref "COL9.") (pin "7") (pinfunction "D_7") (pintype "passive"))
      (node (ref "COL9.") (pin "8") (pinfunction "D_8") (pintype "passive"))
      (node (ref "X1") (pin "C14") (pinfunction "C14_C14") (pintype "passive"))
    )
    (net (code "119") (name "Net-(COL10.A-D-Pad7)") (class "Default")
      (node (ref "COL10.") (pin "5") (pinfunction "D_5") (pintype "passive"))
      (node (ref "COL10.") (pin "6") (pinfunction "D_6") (pintype "passive"))
      (node (ref "COL10.") (pin "7") (pinfunction "D_7") (pintype "passive"))
      (node (ref "COL10.") (pin "8") (pinfunction "D_8") (pintype "passive"))
      (node (ref "X1") (pin "A15") (pinfunction "A15_A15") (pintype "passive"))
    )
    (net (code "120") (name "Net-(COL11.A-D-Pad7)") (class "Default")
      (node (ref "COL11.") (pin "5") (pinfunction "D_5") (pintype "passive"))
      (node (ref "COL11.") (pin "6") (pinfunction "D_6") (pintype "passive"))
      (node (ref "COL11.") (pin "7") (pinfunction "D_7") (pintype "passive"))
      (node (ref "COL11.") (pin "8") (pinfunction "D_8") (pintype "passive"))
      (node (ref "X1") (pin "C15") (pinfunction "C15_C15") (pintype "passive"))
    )
    (net (code "121") (name "Net-(COL12.A-D-Pad7)") (class "Default")
      (node (ref "COL12.") (pin "5") (pinfunction "D_5") (pintype "passive"))
      (node (ref "COL12.") (pin "6") (pinfunction "D_6") (pintype "passive"))
      (node (ref "COL12.") (pin "7") (pinfunction "D_7") (pintype "passive"))
      (node (ref "COL12.") (pin "8") (pinfunction "D_8") (pintype "passive"))
      (node (ref "X1") (pin "A16") (pinfunction "A16_A16") (pintype "passive"))
    )
    (net (code "122") (name "Net-(COL13.A-D-Pad7)") (class "Default")
      (node (ref "COL13.") (pin "5") (pinfunction "D_5") (pintype "passive"))
      (node (ref "COL13.") (pin "6") (pinfunction "D_6") (pintype "passive"))
      (node (ref "COL13.") (pin "7") (pinfunction "D_7") (pintype "passive"))
      (node (ref "COL13.") (pin "8") (pinfunction "D_8") (pintype "passive"))
      (node (ref "X1") (pin "C16") (pinfunction "C16_C16") (pintype "passive"))
    )
    (net (code "123") (name "Net-(COL14.A-D-Pad7)") (class "Default")
      (node (ref "COL14.") (pin "5") (pinfunction "D_5") (pintype "passive"))
      (node (ref "COL14.") (pin "6") (pinfunction "D_6") (pintype "passive"))
      (node (ref "COL14.") (pin "7") (pinfunction "D_7") (pintype "passive"))
      (node (ref "COL14.") (pin "8") (pinfunction "D_8") (pintype "passive"))
      (node (ref "X1") (pin "A17") (pinfunction "A17_A17") (pintype "passive"))
    )
    (net (code "124") (name "Net-(COL15.A-D-Pad7)") (class "Default")
      (node (ref "COL15.") (pin "5") (pinfunction "D_5") (pintype "passive"))
      (node (ref "COL15.") (pin "6") (pinfunction "D_6") (pintype "passive"))
      (node (ref "COL15.") (pin "7") (pinfunction "D_7") (pintype "passive"))
      (node (ref "COL15.") (pin "8") (pinfunction "D_8") (pintype "passive"))
      (node (ref "X1") (pin "C17") (pinfunction "C17_C17") (pintype "passive"))
    )
    (net (code "125") (name "Net-(COL16.A-D-Pad7)") (class "Default")
      (node (ref "COL16.") (pin "5") (pinfunction "D_5") (pintype "passive"))
      (node (ref "COL16.") (pin "6") (pinfunction "D_6") (pintype "passive"))
      (node (ref "COL16.") (pin "7") (pinfunction "D_7") (pintype "passive"))
      (node (ref "COL16.") (pin "8") (pinfunction "D_8") (pintype "passive"))
      (node (ref "X1") (pin "A18") (pinfunction "A18_A18") (pintype "passive"))
    )
    (net (code "126") (name "Net-(COL17.A-D-Pad7)") (class "Default")
      (node (ref "COL17.") (pin "5") (pinfunction "D_5") (pintype "passive"))
      (node (ref "COL17.") (pin "6") (pinfunction "D_6") (pintype "passive"))
      (node (ref "COL17.") (pin "7") (pinfunction "D_7") (pintype "passive"))
      (node (ref "COL17.") (pin "8") (pinfunction "D_8") (pintype "passive"))
      (node (ref "X1") (pin "C18") (pinfunction "C18_C18") (pintype "passive"))
    )
    (net (code "127") (name "Net-(COL18.A-D-Pad7)") (class "Default")
      (node (ref "COL18.") (pin "5") (pinfunction "D_5") (pintype "passive"))
      (node (ref "COL18.") (pin "6") (pinfunction "D_6") (pintype "passive"))
      (node (ref "COL18.") (pin "7") (pinfunction "D_7") (pintype "passive"))
      (node (ref "COL18.") (pin "8") (pinfunction "D_8") (pintype "passive"))
      (node (ref "X1") (pin "A19") (pinfunction "A19_A19") (pintype "passive"))
    )
    (net (code "128") (name "Net-(COL19.A-D-Pad7)") (class "Default")
      (node (ref "COL19.") (pin "5") (pinfunction "D_5") (pintype "passive"))
      (node (ref "COL19.") (pin "6") (pinfunction "D_6") (pintype "passive"))
      (node (ref "COL19.") (pin "7") (pinfunction "D_7") (pintype "passive"))
      (node (ref "COL19.") (pin "8") (pinfunction "D_8") (pintype "passive"))
      (node (ref "X1") (pin "C19") (pinfunction "C19_C19") (pintype "passive"))
    )
    (net (code "129") (name "Net-(COL20.A-D-Pad7)") (class "Default")
      (node (ref "COL20.") (pin "5") (pinfunction "D_5") (pintype "passive"))
      (node (ref "COL20.") (pin "6") (pinfunction "D_6") (pintype "passive"))
      (node (ref "COL20.") (pin "7") (pinfunction "D_7") (pintype "passive"))
      (node (ref "COL20.") (pin "8") (pinfunction "D_8") (pintype "passive"))
      (node (ref "X1") (pin "A20") (pinfunction "A20_A20") (pintype "passive"))
    )
    (net (code "130") (name "Net-(COL21.A-D-Pad7)") (class "Default")
      (node (ref "COL21.") (pin "5") (pinfunction "D_5") (pintype "passive"))
      (node (ref "COL21.") (pin "6") (pinfunction "D_6") (pintype "passive"))
      (node (ref "COL21.") (pin "7") (pinfunction "D_7") (pintype "passive"))
      (node (ref "COL21.") (pin "8") (pinfunction "D_8") (pintype "passive"))
      (node (ref "X1") (pin "C20") (pinfunction "C20_C20") (pintype "passive"))
    )
    (net (code "131") (name "Net-(COL22.A-D-Pad7)") (class "Default")
      (node (ref "COL22.") (pin "5") (pinfunction "D_5") (pintype "passive"))
      (node (ref "COL22.") (pin "6") (pinfunction "D_6") (pintype "passive"))
      (node (ref "COL22.") (pin "7") (pinfunction "D_7") (pintype "passive"))
      (node (ref "COL22.") (pin "8") (pinfunction "D_8") (pintype "passive"))
      (node (ref "X1") (pin "A21") (pinfunction "A21_A21") (pintype "passive"))
    )
    (net (code "132") (name "Net-(COL23.A-D-Pad7)") (class "Default")
      (node (ref "COL23.") (pin "5") (pinfunction "D_5") (pintype "passive"))
      (node (ref "COL23.") (pin "6") (pinfunction "D_6") (pintype "passive"))
      (node (ref "COL23.") (pin "7") (pinfunction "D_7") (pintype "passive"))
      (node (ref "COL23.") (pin "8") (pinfunction "D_8") (pintype "passive"))
      (node (ref "X1") (pin "C21") (pinfunction "C21_C21") (pintype "passive"))
    )
    (net (code "133") (name "Net-(COL24.A-D-Pad7)") (class "Default")
      (node (ref "COL24.") (pin "5") (pinfunction "D_5") (pintype "passive"))
      (node (ref "COL24.") (pin "6") (pinfunction "D_6") (pintype "passive"))
      (node (ref "COL24.") (pin "7") (pinfunction "D_7") (pintype "passive"))
      (node (ref "COL24.") (pin "8") (pinfunction "D_8") (pintype "passive"))
      (node (ref "X1") (pin "A22") (pinfunction "A22_A22") (pintype "passive"))
    )
    (net (code "134") (name "Net-(COL25.A-D-Pad7)") (class "Default")
      (node (ref "COL25.") (pin "5") (pinfunction "D_5") (pintype "passive"))
      (node (ref "COL25.") (pin "6") (pinfunction "D_6") (pintype "passive"))
      (node (ref "COL25.") (pin "7") (pinfunction "D_7") (pintype "passive"))
      (node (ref "COL25.") (pin "8") (pinfunction "D_8") (pintype "passive"))
      (node (ref "X1") (pin "C22") (pinfunction "C22_C22") (pintype "passive"))
    )
    (net (code "135") (name "Net-(COL26.A-D-Pad7)") (class "Default")
      (node (ref "COL26.") (pin "5") (pinfunction "D_5") (pintype "passive"))
      (node (ref "COL26.") (pin "6") (pinfunction "D_6") (pintype "passive"))
      (node (ref "COL26.") (pin "7") (pinfunction "D_7") (pintype "passive"))
      (node (ref "COL26.") (pin "8") (pinfunction "D_8") (pintype "passive"))
      (node (ref "X1") (pin "A23") (pinfunction "A23_A23") (pintype "passive"))
    )
    (net (code "136") (name "Net-(COL27.A-D-Pad7)") (class "Default")
      (node (ref "COL27.") (pin "5") (pinfunction "D_5") (pintype "passive"))
      (node (ref "COL27.") (pin "6") (pinfunction "D_6") (pintype "passive"))
      (node (ref "COL27.") (pin "7") (pinfunction "D_7") (pintype "passive"))
      (node (ref "COL27.") (pin "8") (pinfunction "D_8") (pintype "passive"))
      (node (ref "X1") (pin "C23") (pinfunction "C23_C23") (pintype "passive"))
    )
    (net (code "137") (name "Net-(COL28.A-D-Pad7)") (class "Default")
      (node (ref "COL28.") (pin "5") (pinfunction "D_5") (pintype "passive"))
      (node (ref "COL28.") (pin "6") (pinfunction "D_6") (pintype "passive"))
      (node (ref "COL28.") (pin "7") (pinfunction "D_7") (pintype "passive"))
      (node (ref "COL28.") (pin "8") (pinfunction "D_8") (pintype "passive"))
      (node (ref "X1") (pin "A24") (pinfunction "A24_A24") (pintype "passive"))
    )
    (net (code "138") (name "Net-(COL29.A-D-Pad7)") (class "Default")
      (node (ref "COL29.") (pin "5") (pinfunction "D_5") (pintype "passive"))
      (node (ref "COL29.") (pin "6") (pinfunction "D_6") (pintype "passive"))
      (node (ref "COL29.") (pin "7") (pinfunction "D_7") (pintype "passive"))
      (node (ref "COL29.") (pin "8") (pinfunction "D_8") (pintype "passive"))
      (node (ref "X1") (pin "C24") (pinfunction "C24_C24") (pintype "passive"))
    )
    (net (code "139") (name "Net-(COL30.A-D-Pad7)") (class "Default")
      (node (ref "COL30.") (pin "5") (pinfunction "D_5") (pintype "passive"))
      (node (ref "COL30.") (pin "6") (pinfunction "D_6") (pintype "passive"))
      (node (ref "COL30.") (pin "7") (pinfunction "D_7") (pintype "passive"))
      (node (ref "COL30.") (pin "8") (pinfunction "D_8") (pintype "passive"))
      (node (ref "X1") (pin "A25") (pinfunction "A25_A25") (pintype "passive"))
    )
    (net (code "140") (name "Net-(COL31.A-D-Pad7)") (class "Default")
      (node (ref "COL31.") (pin "5") (pinfunction "D_5") (pintype "passive"))
      (node (ref "COL31.") (pin "6") (pinfunction "D_6") (pintype "passive"))
      (node (ref "COL31.") (pin "7") (pinfunction "D_7") (pintype "passive"))
      (node (ref "COL31.") (pin "8") (pinfunction "D_8") (pintype "passive"))
      (node (ref "X1") (pin "C25") (pinfunction "C25_C25") (pintype "passive"))
    )
    (net (code "141") (name "Net-(COL32.A-D-Pad7)") (class "Default")
      (node (ref "COL32.") (pin "5") (pinfunction "D_5") (pintype "passive"))
      (node (ref "COL32.") (pin "6") (pinfunction "D_6") (pintype "passive"))
      (node (ref "COL32.") (pin "7") (pinfunction "D_7") (pintype "passive"))
      (node (ref "COL32.") (pin "8") (pinfunction "D_8") (pintype "passive"))
      (node (ref "X1") (pin "A26") (pinfunction "A26_A26") (pintype "passive"))
    )
    (net (code "142") (name "Net-(COL33.A-D-Pad7)") (class "Default")
      (node (ref "COL33.") (pin "5") (pinfunction "D_5") (pintype "passive"))
      (node (ref "COL33.") (pin "6") (pinfunction "D_6") (pintype "passive"))
      (node (ref "COL33.") (pin "7") (pinfunction "D_7") (pintype "passive"))
      (node (ref "COL33.") (pin "8") (pinfunction "D_8") (pintype "passive"))
      (node (ref "X1") (pin "C26") (pinfunction "C26_C26") (pintype "passive"))
    )
    (net (code "143") (name "Net-(COL34.A-D-Pad7)") (class "Default")
      (node (ref "COL34.") (pin "5") (pinfunction "D_5") (pintype "passive"))
      (node (ref "COL34.") (pin "6") (pinfunction "D_6") (pintype "passive"))
      (node (ref "COL34.") (pin "7") (pinfunction "D_7") (pintype "passive"))
      (node (ref "COL34.") (pin "8") (pinfunction "D_8") (pintype "passive"))
      (node (ref "X1") (pin "A27") (pinfunction "A27_A27") (pintype "passive"))
    )
    (net (code "144") (name "Net-(COL35.A-D-Pad7)") (class "Default")
      (node (ref "COL35.") (pin "5") (pinfunction "D_5") (pintype "passive"))
      (node (ref "COL35.") (pin "6") (pinfunction "D_6") (pintype "passive"))
      (node (ref "COL35.") (pin "7") (pinfunction "D_7") (pintype "passive"))
      (node (ref "COL35.") (pin "8") (pinfunction "D_8") (pintype "passive"))
      (node (ref "X1") (pin "C27") (pinfunction "C27_C27") (pintype "passive"))
    )
    (net (code "145") (name "Net-(COL36.A-D-Pad7)") (class "Default")
      (node (ref "COL36.") (pin "5") (pinfunction "D_5") (pintype "passive"))
      (node (ref "COL36.") (pin "6") (pinfunction "D_6") (pintype "passive"))
      (node (ref "COL36.") (pin "7") (pinfunction "D_7") (pintype "passive"))
      (node (ref "COL36.") (pin "8") (pinfunction "D_8") (pintype "passive"))
      (node (ref "X1") (pin "A28") (pinfunction "A28_A28") (pintype "passive"))
    )
    (net (code "146") (name "Net-(COL37.A-D-Pad7)") (class "Default")
      (node (ref "COL37.") (pin "5") (pinfunction "D_5") (pintype "passive"))
      (node (ref "COL37.") (pin "6") (pinfunction "D_6") (pintype "passive"))
      (node (ref "COL37.") (pin "7") (pinfunction "D_7") (pintype "passive"))
      (node (ref "COL37.") (pin "8") (pinfunction "D_8") (pintype "passive"))
      (node (ref "X1") (pin "C28") (pinfunction "C28_C28") (pintype "passive"))
    )
    (net (code "147") (name "Net-(COL38.A-D-Pad7)") (class "Default")
      (node (ref "COL38.") (pin "5") (pinfunction "D_5") (pintype "passive"))
      (node (ref "COL38.") (pin "6") (pinfunction "D_6") (pintype "passive"))
      (node (ref "COL38.") (pin "7") (pinfunction "D_7") (pintype "passive"))
      (node (ref "COL38.") (pin "8") (pinfunction "D_8") (pintype "passive"))
      (node (ref "X1") (pin "A29") (pinfunction "A29_A29") (pintype "passive"))
    )
    (net (code "148") (name "Net-(COL39.A-D-Pad7)") (class "Default")
      (node (ref "COL39.") (pin "5") (pinfunction "D_5") (pintype "passive"))
      (node (ref "COL39.") (pin "6") (pinfunction "D_6") (pintype "passive"))
      (node (ref "COL39.") (pin "7") (pinfunction "D_7") (pintype "passive"))
      (node (ref "COL39.") (pin "8") (pinfunction "D_8") (pintype "passive"))
      (node (ref "X1") (pin "C29") (pinfunction "C29_C29") (pintype "passive"))
    )
    (net (code "149") (name "Net-(COL40.A-D-Pad7)") (class "Default")
      (node (ref "COL40.") (pin "5") (pinfunction "D_5") (pintype "passive"))
      (node (ref "COL40.") (pin "6") (pinfunction "D_6") (pintype "passive"))
      (node (ref "COL40.") (pin "7") (pinfunction "D_7") (pintype "passive"))
      (node (ref "COL40.") (pin "8") (pinfunction "D_8") (pintype "passive"))
      (node (ref "X1") (pin "A30") (pinfunction "A30_A30") (pintype "passive"))
    )
    (net (code "150") (name "Net-(COL41.A-D-Pad7)") (class "Default")
      (node (ref "COL41.") (pin "5") (pinfunction "D_5") (pintype "passive"))
      (node (ref "COL41.") (pin "6") (pinfunction "D_6") (pintype "passive"))
      (node (ref "COL41.") (pin "7") (pinfunction "D_7") (pintype "passive"))
      (node (ref "COL41.") (pin "8") (pinfunction "D_8") (pintype "passive"))
      (node (ref "X1") (pin "C30") (pinfunction "C30_C30") (pintype "passive"))
    )
    (net (code "151") (name "Net-(COL42.A-D-Pad7)") (class "Default")
      (node (ref "COL42.") (pin "5") (pinfunction "D_5") (pintype "passive"))
      (node (ref "COL42.") (pin "6") (pinfunction "D_6") (pintype "passive"))
      (node (ref "COL42.") (pin "7") (pinfunction "D_7") (pintype "passive"))
      (node (ref "COL42.") (pin "8") (pinfunction "D_8") (pintype "passive"))
      (node (ref "X1") (pin "A31") (pinfunction "A31_A31") (pintype "passive"))
    )
    (net (code "152") (name "Net-(COL43.A-D-Pad7)") (class "Default")
      (node (ref "COL43.") (pin "5") (pinfunction "D_5") (pintype "passive"))
      (node (ref "COL43.") (pin "6") (pinfunction "D_6") (pintype "passive"))
      (node (ref "COL43.") (pin "7") (pinfunction "D_7") (pintype "passive"))
      (node (ref "COL43.") (pin "8") (pinfunction "D_8") (pintype "passive"))
      (node (ref "X1") (pin "C31") (pinfunction "C31_C31") (pintype "passive"))
    )
    (net (code "153") (name "Net-(COL44.A-D-Pad7)") (class "Default")
      (node (ref "COL44.") (pin "5") (pinfunction "D_5") (pintype "passive"))
      (node (ref "COL44.") (pin "6") (pinfunction "D_6") (pintype "passive"))
      (node (ref "COL44.") (pin "7") (pinfunction "D_7") (pintype "passive"))
      (node (ref "COL44.") (pin "8") (pinfunction "D_8") (pintype "passive"))
      (node (ref "X1") (pin "A32") (pinfunction "A32_A32") (pintype "passive"))
    )
    (net (code "154") (name "Net-(COL45.A-D-Pad7)") (class "Default")
      (node (ref "COL45.") (pin "5") (pinfunction "D_5") (pintype "passive"))
      (node (ref "COL45.") (pin "6") (pinfunction "D_6") (pintype "passive"))
      (node (ref "COL45.") (pin "7") (pinfunction "D_7") (pintype "passive"))
      (node (ref "COL45.") (pin "8") (pinfunction "D_8") (pintype "passive"))
      (node (ref "X1") (pin "C32") (pinfunction "C32_C32") (pintype "passive"))
    )
    (net (code "155") (name "Net-(ROW1.A-D-Pad7)") (class "Default")
      (node (ref "ROW1.") (pin "7") (pinfunction "D_7") (pintype "passive"))
      (node (ref "ROW1.") (pin "8") (pinfunction "D_8") (pintype "passive"))
      (node (ref "X1") (pin "C3") (pinfunction "C3_C3") (pintype "passive"))
    )
    (net (code "156") (name "Net-(ROW1.B-D-Pad5)") (class "Default")
      (node (ref "ROW1.") (pin "5") (pinfunction "D_5") (pintype "passive"))
      (node (ref "ROW1.") (pin "6") (pinfunction "D_6") (pintype "passive"))
      (node (ref "X1") (pin "A3") (pinfunction "A3_A3") (pintype "passive"))
    )
    (net (code "157") (name "Net-(ROW2.A-D-Pad7)") (class "Default")
      (node (ref "ROW2.") (pin "7") (pinfunction "D_7") (pintype "passive"))
      (node (ref "ROW2.") (pin "8") (pinfunction "D_8") (pintype "passive"))
      (node (ref "X1") (pin "C4") (pinfunction "C4_C4") (pintype "passive"))
    )
    (net (code "158") (name "Net-(ROW2.B-D-Pad5)") (class "Default")
      (node (ref "ROW2.") (pin "5") (pinfunction "D_5") (pintype "passive"))
      (node (ref "ROW2.") (pin "6") (pinfunction "D_6") (pintype "passive"))
      (node (ref "X1") (pin "A4") (pinfunction "A4_A4") (pintype "passive"))
    )
    (net (code "159") (name "Net-(ROW3.A-D-Pad7)") (class "Default")
      (node (ref "ROW3.") (pin "7") (pinfunction "D_7") (pintype "passive"))
      (node (ref "ROW3.") (pin "8") (pinfunction "D_8") (pintype "passive"))
      (node (ref "X1") (pin "C5") (pinfunction "C5_C5") (pintype "passive"))
    )
    (net (code "160") (name "Net-(ROW3.B-D-Pad5)") (class "Default")
      (node (ref "ROW3.") (pin "5") (pinfunction "D_5") (pintype "passive"))
      (node (ref "ROW3.") (pin "6") (pinfunction "D_6") (pintype "passive"))
      (node (ref "X1") (pin "A5") (pinfunction "A5_A5") (pintype "passive"))
    )
    (net (code "161") (name "Net-(ROW4.A-D-Pad7)") (class "Default")
      (node (ref "ROW4.") (pin "7") (pinfunction "D_7") (pintype "passive"))
      (node (ref "ROW4.") (pin "8") (pinfunction "D_8") (pintype "passive"))
      (node (ref "X1") (pin "C6") (pinfunction "C6_C6") (pintype "passive"))
    )
    (net (code "162") (name "Net-(ROW4.B-D-Pad5)") (class "Default")
      (node (ref "ROW4.") (pin "5") (pinfunction "D_5") (pintype "passive"))
      (node (ref "ROW4.") (pin "6") (pinfunction "D_6") (pintype "passive"))
      (node (ref "X1") (pin "A6") (pinfunction "A6_A6") (pintype "passive"))
    )
    (net (code "163") (name "Net-(ROW5.A-D-Pad7)") (class "Default")
      (node (ref "ROW5.") (pin "7") (pinfunction "D_7") (pintype "passive"))
      (node (ref "ROW5.") (pin "8") (pinfunction "D_8") (pintype "passive"))
      (node (ref "X1") (pin "C7") (pinfunction "C7_C7") (pintype "passive"))
    )
    (net (code "164") (name "Net-(ROW5.B-D-Pad5)") (class "Default")
      (node (ref "ROW5.") (pin "5") (pinfunction "D_5") (pintype "passive"))
      (node (ref "ROW5.") (pin "6") (pinfunction "D_6") (pintype "passive"))
      (node (ref "X1") (pin "A7") (pinfunction "A7_A7") (pintype "passive"))
    )
    (net (code "165") (name "Net-(ROW6.A-D-Pad7)") (class "Default")
      (node (ref "ROW6.") (pin "7") (pinfunction "D_7") (pintype "passive"))
      (node (ref "ROW6.") (pin "8") (pinfunction "D_8") (pintype "passive"))
      (node (ref "X1") (pin "C8") (pinfunction "C8_C8") (pintype "passive"))
    )
    (net (code "166") (name "Net-(ROW6.B-D-Pad5)") (class "Default")
      (node (ref "ROW6.") (pin "5") (pinfunction "D_5") (pintype "passive"))
      (node (ref "ROW6.") (pin "6") (pinfunction "D_6") (pintype "passive"))
      (node (ref "X1") (pin "A8") (pinfunction "A8_A8") (pintype "passive"))
    )
    (net (code "167") (name "Net-(ROW7.A-D-Pad7)") (class "Default")
      (node (ref "ROW7.") (pin "7") (pinfunction "D_7") (pintype "passive"))
      (node (ref "ROW7.") (pin "8") (pinfunction "D_8") (pintype "passive"))
      (node (ref "X1") (pin "C9") (pinfunction "C9_C9") (pintype "passive"))
    )
    (net (code "168") (name "Net-(ROW7.B-D-Pad5)") (class "Default")
      (node (ref "ROW7.") (pin "5") (pinfunction "D_5") (pintype "passive"))
      (node (ref "ROW7.") (pin "6") (pinfunction "D_6") (pintype "passive"))
      (node (ref "X1") (pin "A9") (pinfunction "A9_A9") (pintype "passive"))
    )
    (net (code "169") (name "Net-(SR1A-QH*)") (class "Default")
      (node (ref "SR1") (pin "9") (pinfunction "QH*_9") (pintype "tri_state"))
      (node (ref "SR2") (pin "14") (pinfunction "SER_14") (pintype "input"))
    )
    (net (code "170") (name "Net-(SR1A-SER)") (class "Default")
      (node (ref "JP1") (pin "7") (pinfunction "7_7") (pintype "passive"))
      (node (ref "SR1") (pin "14") (pinfunction "SER_14") (pintype "input"))
    )
    (net (code "171") (name "Net-(SR2A-QH*)") (class "Default")
      (node (ref "SR2") (pin "9") (pinfunction "QH*_9") (pintype "tri_state"))
      (node (ref "SR3") (pin "14") (pinfunction "SER_14") (pintype "input"))
    )
    (net (code "172") (name "Net-(SR3A-QH*)") (class "Default")
      (node (ref "SR3") (pin "9") (pinfunction "QH*_9") (pintype "tri_state"))
      (node (ref "SR4") (pin "14") (pinfunction "SER_14") (pintype "input"))
    )
    (net (code "173") (name "Net-(SR4A-QH*)") (class "Default")
      (node (ref "SR4") (pin "9") (pinfunction "QH*_9") (pintype "tri_state"))
      (node (ref "SR5") (pin "14") (pinfunction "SER_14") (pintype "input"))
    )
    (net (code "174") (name "Net-(SR5A-QH*)") (class "Default")
      (node (ref "SR5") (pin "9") (pinfunction "QH*_9") (pintype "tri_state"))
      (node (ref "SR6") (pin "14") (pinfunction "SER_14") (pintype "input"))
    )
    (net (code "175") (name "Net-(SR6A-QH*)") (class "Default")
      (node (ref "SR6") (pin "9") (pinfunction "QH*_9") (pintype "tri_state"))
      (node (ref "SR7") (pin "14") (pinfunction "SER_14") (pintype "input"))
    )
    (net (code "176") (name "Net-(SR7A-QH*)") (class "Default")
      (node (ref "SR7") (pin "9") (pinfunction "QH*_9") (pintype "tri_state"))
      (node (ref "SR8") (pin "14") (pinfunction "SER_14") (pintype "input"))
    )
    (net (code "177") (name "Net-(SR8A-QH*)") (class "Default")
      (node (ref "SR8") (pin "9") (pinfunction "QH*_9") (pintype "tri_state"))
      (node (ref "SR9") (pin "14") (pinfunction "SER_14") (pintype "input"))
    )
    (net (code "178") (name "Net-(SR10A-QH*)") (class "Default")
      (node (ref "SR10") (pin "9") (pinfunction "QH*_9") (pintype "tri_state"))
      (node (ref "SR11") (pin "14") (pinfunction "SER_14") (pintype "input"))
    )
    (net (code "179") (name "Net-(SR10A-SER)") (class "Default")
      (node (ref "SR10") (pin "14") (pinfunction "SER_14") (pintype "input"))
      (node (ref "SR9") (pin "9") (pinfunction "QH*_9") (pintype "tri_state"))
    )
    (net (code "180") (name "Net-(SR11A-QH*)") (class "Default")
      (node (ref "SR11") (pin "9") (pinfunction "QH*_9") (pintype "tri_state"))
      (node (ref "SR12") (pin "14") (pinfunction "SER_14") (pintype "input"))
    )
    (net (code "181") (name "Net-(SR12A-QH*)") (class "Default")
      (node (ref "SR12") (pin "9") (pinfunction "QH*_9") (pintype "tri_state"))
      (node (ref "SR13") (pin "14") (pinfunction "SER_14") (pintype "input"))
    )
    (net (code "182") (name "VCC") (class "Default")
      (node (ref "C1") (pin "1") (pinfunction "1_1") (pintype "passive"))
      (node (ref "C10") (pin "1") (pinfunction "1_1") (pintype "passive"))
      (node (ref "C11") (pin "1") (pinfunction "1_1") (pintype "passive"))
      (node (ref "C12") (pin "1") (pinfunction "1_1") (pintype "passive"))
      (node (ref "C13") (pin "1") (pinfunction "1_1") (pintype "passive"))
      (node (ref "C2") (pin "1") (pinfunction "1_1") (pintype "passive"))
      (node (ref "C3") (pin "1") (pinfunction "1_1") (pintype "passive"))
      (node (ref "C4") (pin "1") (pinfunction "1_1") (pintype "passive"))
      (node (ref "C5") (pin "1") (pinfunction "1_1") (pintype "passive"))
      (node (ref "C6") (pin "1") (pinfunction "1_1") (pintype "passive"))
      (node (ref "C7") (pin "1") (pinfunction "1_1") (pintype "passive"))
      (node (ref "C8") (pin "1") (pinfunction "1_1") (pintype "passive"))
      (node (ref "C9") (pin "1") (pinfunction "1_1") (pintype "passive"))
      (node (ref "JP1") (pin "2") (pinfunction "2_2") (pintype "passive"))
      (node (ref "LOGICCAP") (pin "+") (pinfunction "+_+") (pintype "passive"))
      (node (ref "SR1") (pin "10") (pinfunction "SCL_10") (pintype "input"))
      (node (ref "SR10") (pin "10") (pinfunction "SCL_10") (pintype "input"))
      (node (ref "SR11") (pin "10") (pinfunction "SCL_10") (pintype "input"))
      (node (ref "SR12") (pin "10") (pinfunction "SCL_10") (pintype "input"))
      (node (ref "SR13") (pin "10") (pinfunction "SCL_10") (pintype "input"))
      (node (ref "SR2") (pin "10") (pinfunction "SCL_10") (pintype "input"))
      (node (ref "SR3") (pin "10") (pinfunction "SCL_10") (pintype "input"))
      (node (ref "SR4") (pin "10") (pinfunction "SCL_10") (pintype "input"))
      (node (ref "SR5") (pin "10") (pinfunction "SCL_10") (pintype "input"))
      (node (ref "SR6") (pin "10") (pinfunction "SCL_10") (pintype "input"))
      (node (ref "SR7") (pin "10") (pinfunction "SCL_10") (pintype "input"))
      (node (ref "SR8") (pin "10") (pinfunction "SCL_10") (pintype "input"))
      (node (ref "SR9") (pin "10") (pinfunction "SCL_10") (pintype "input"))
    )
    (net (code "183") (name "unconnected-(SR13A-QH*-Pad9)") (class "Default")
      (node (ref "SR13") (pin "9") (pinfunction "QH*_9") (pintype "tri_state"))
    )
    (net (code "184") (name "unconnected-(X1-PadA10)") (class "Default")
      (node (ref "X1") (pin "A10") (pinfunction "A10_A10") (pintype "passive"))
    )
  )
)
